# 8_bit_Right_Rev_A.net
KiCad netlist of a schematic drawn in EAGLE
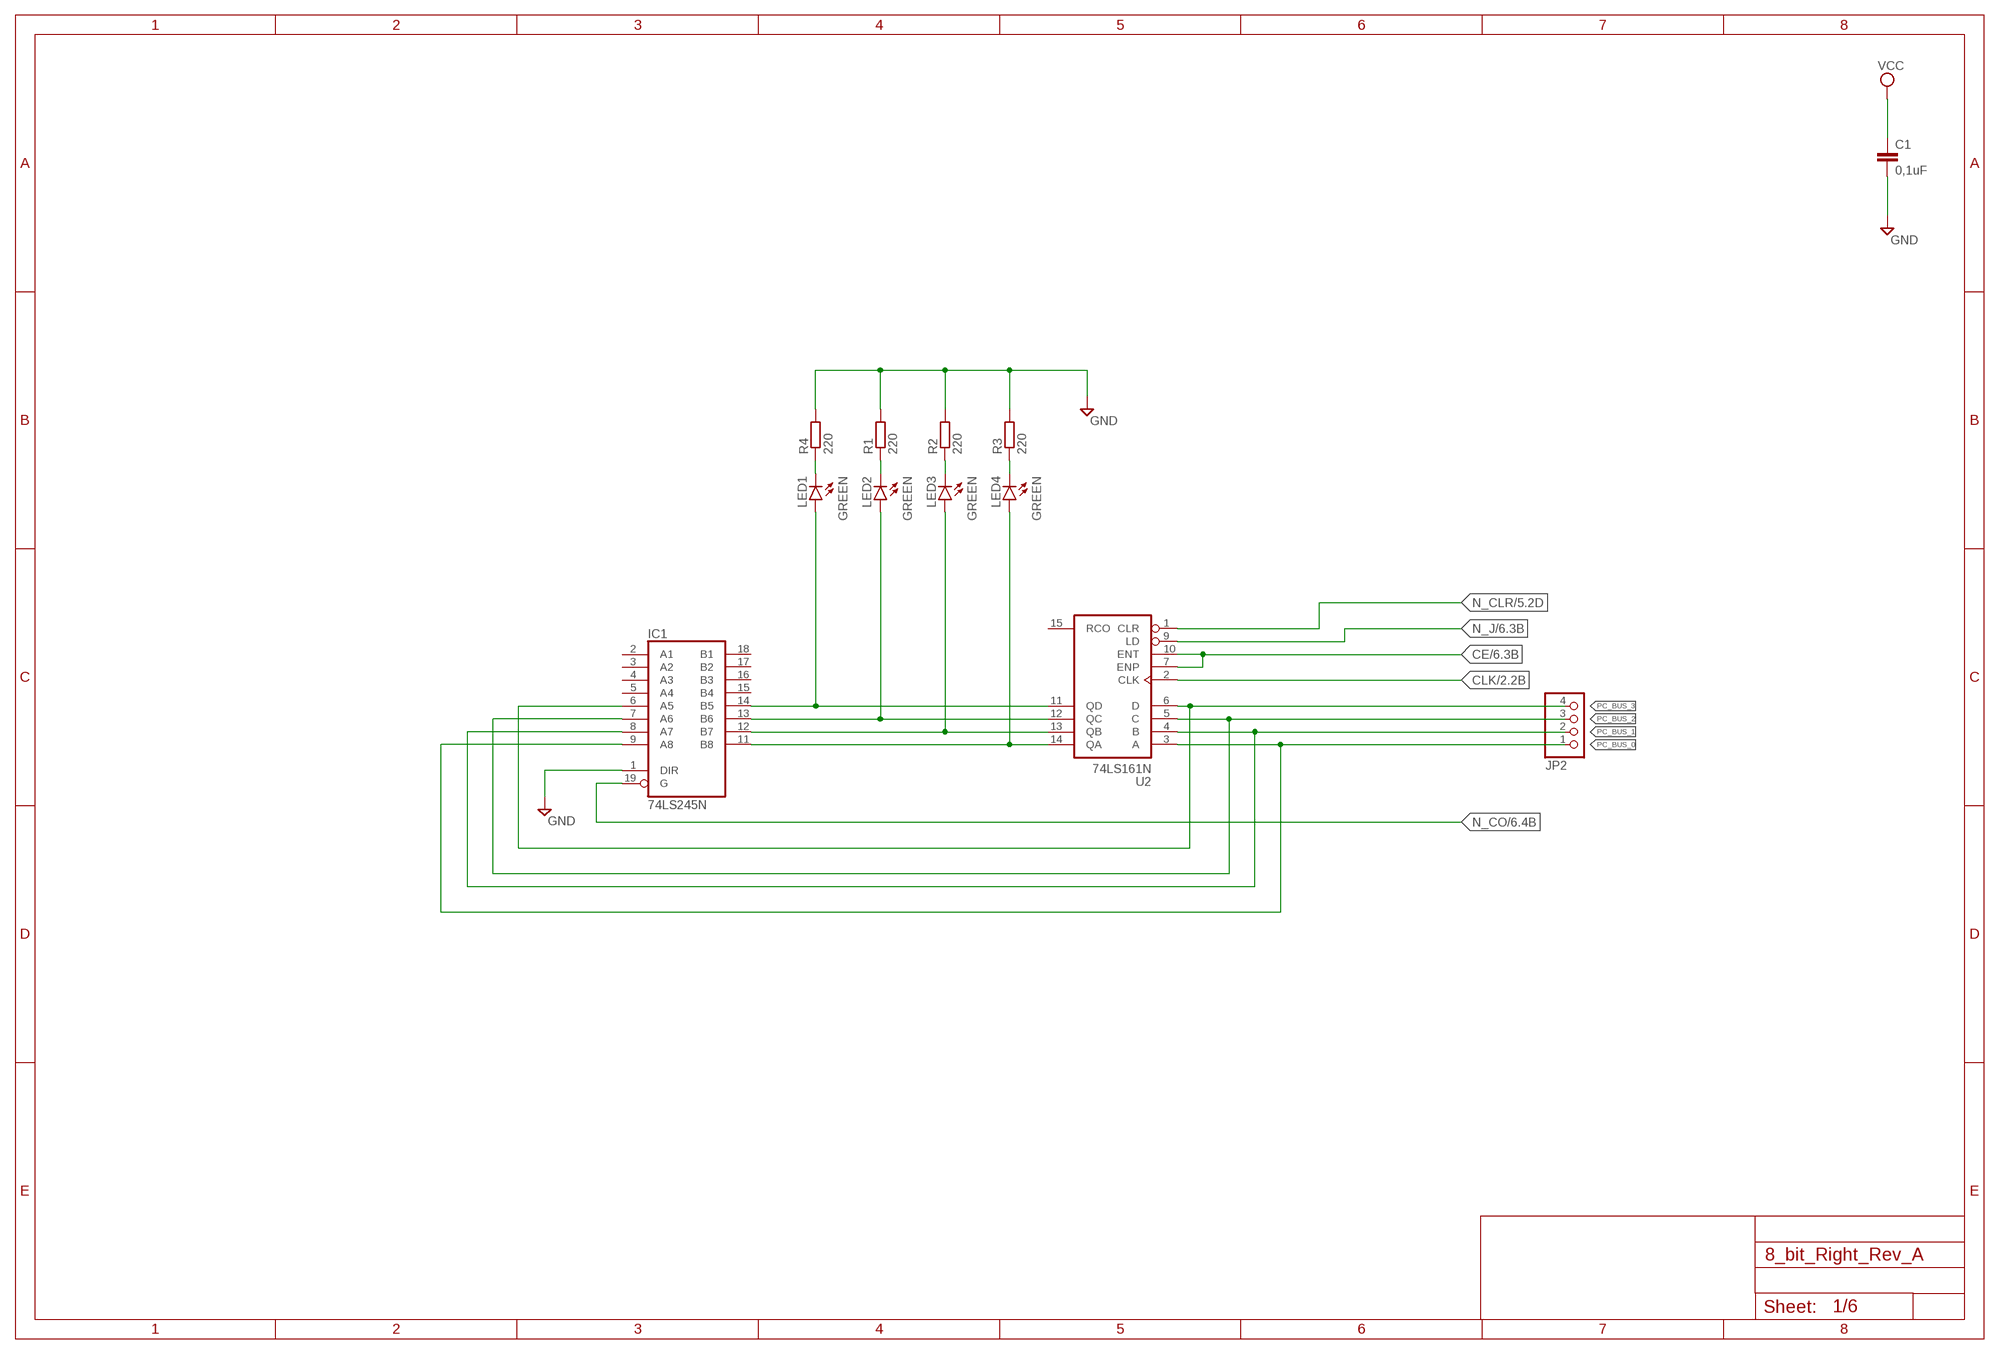
[diagram p0: schematic, sheet 1]
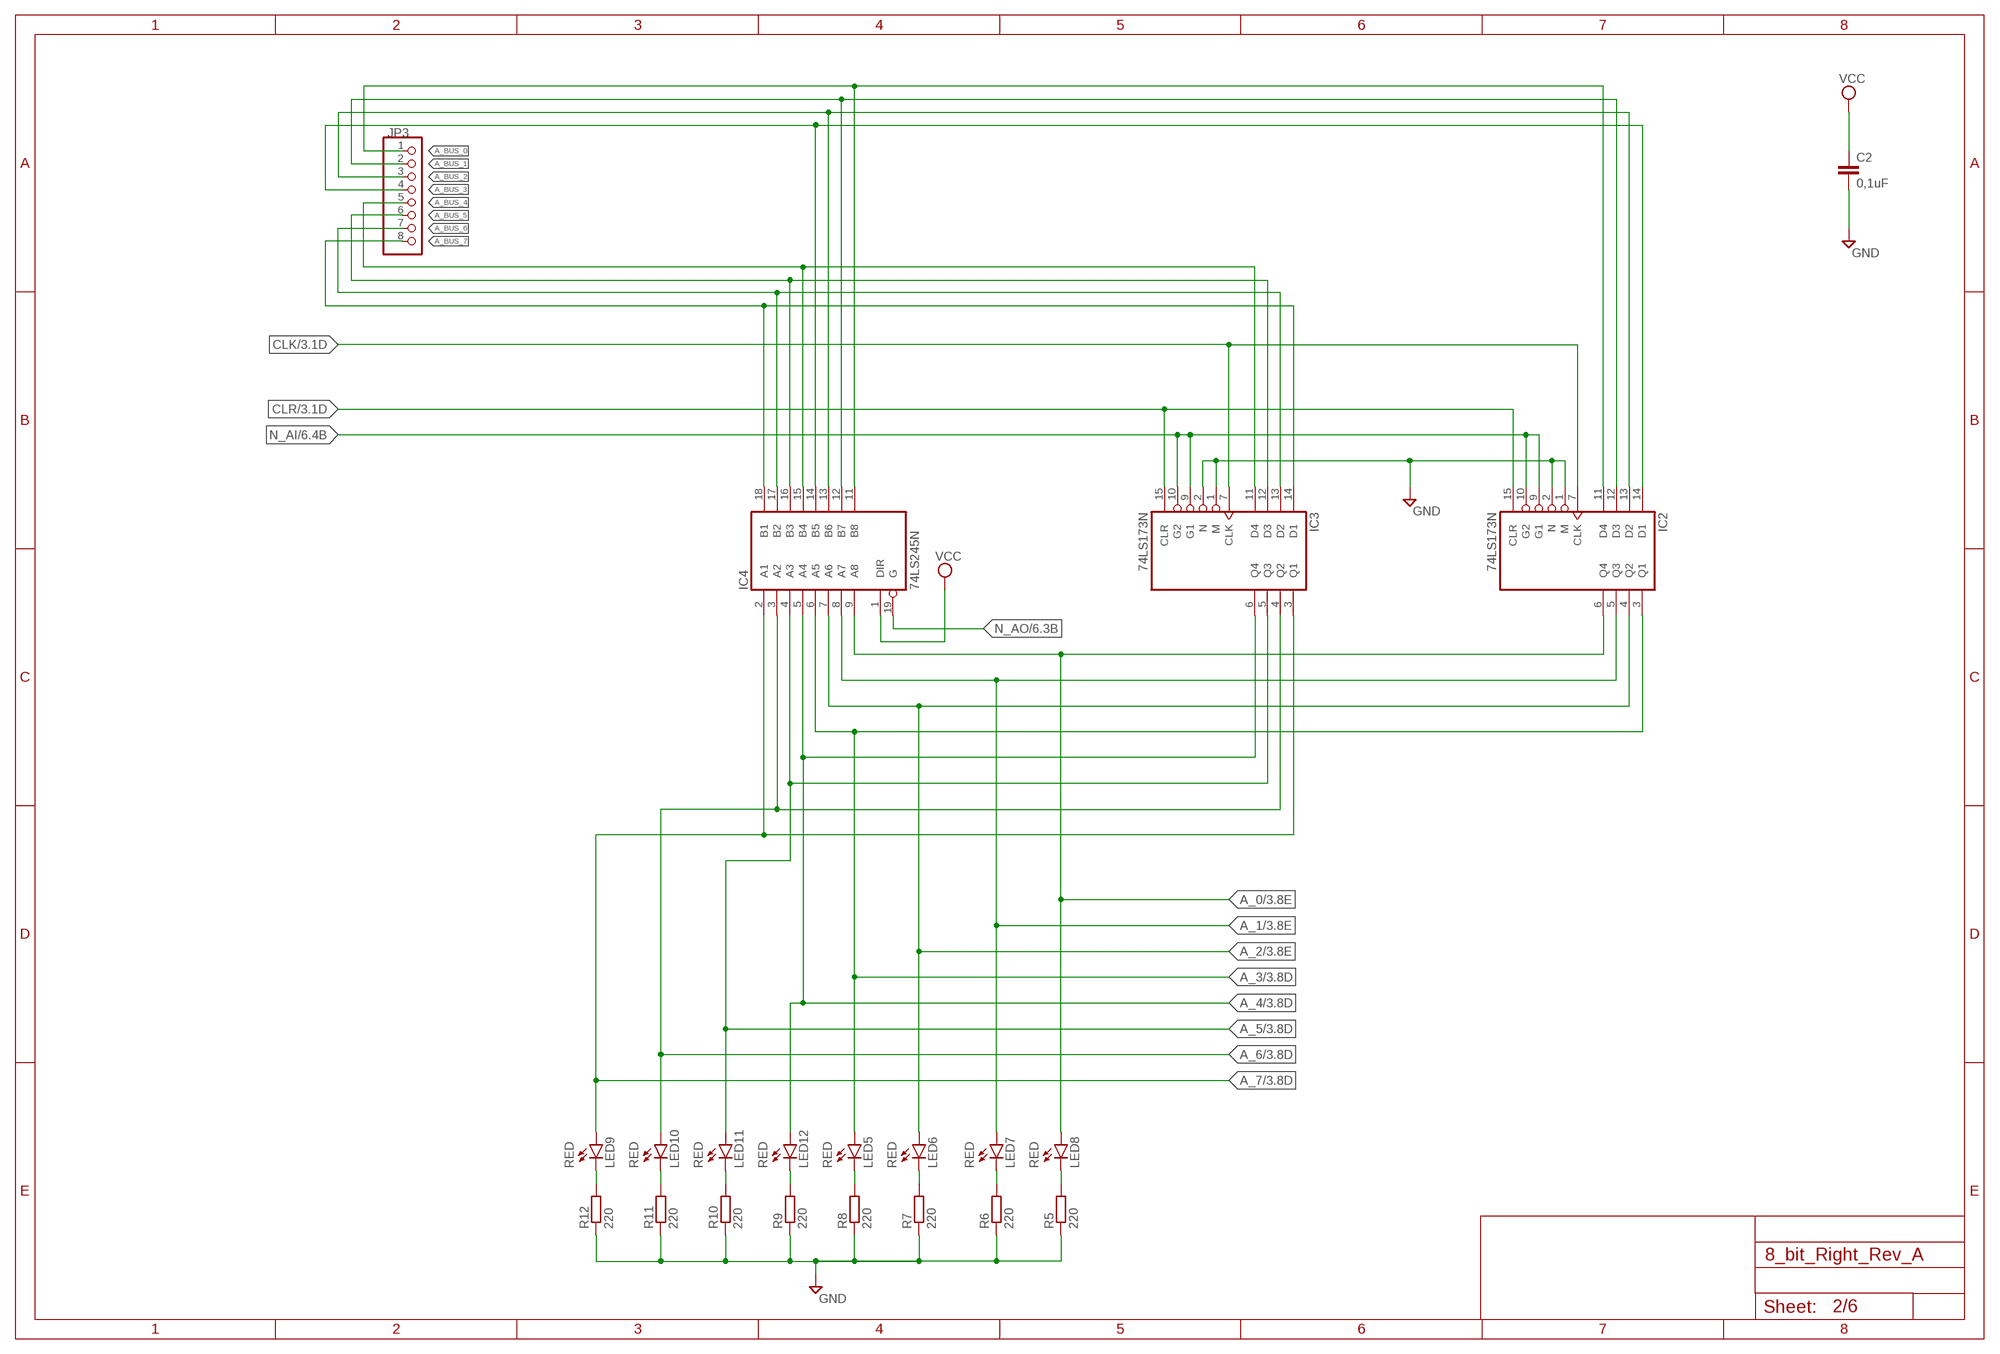
[diagram p1: schematic, sheet 2]
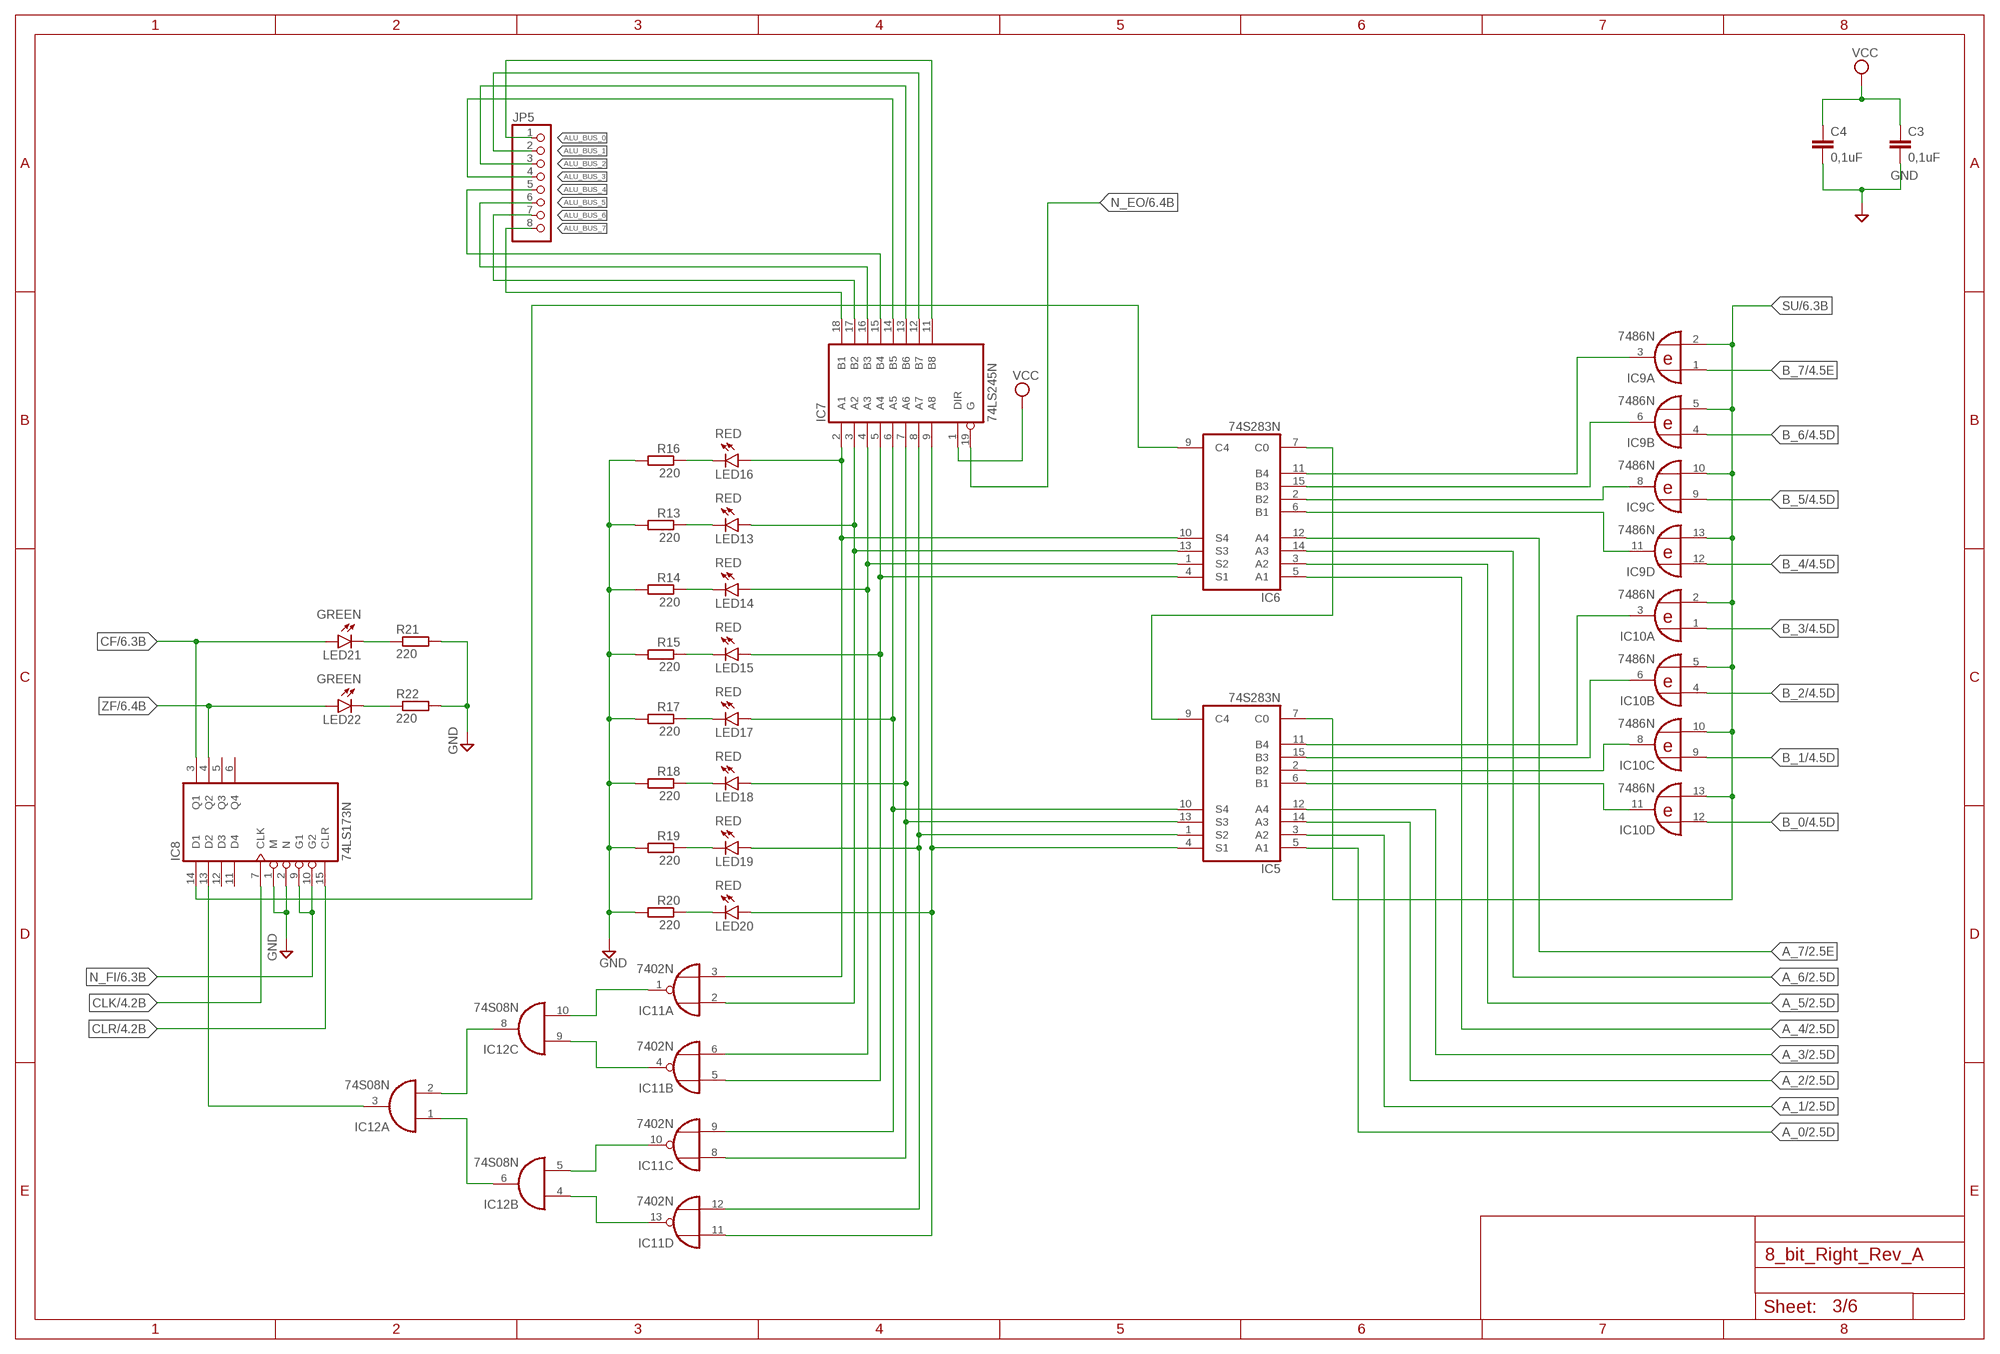
[diagram p2: schematic, sheet 3]
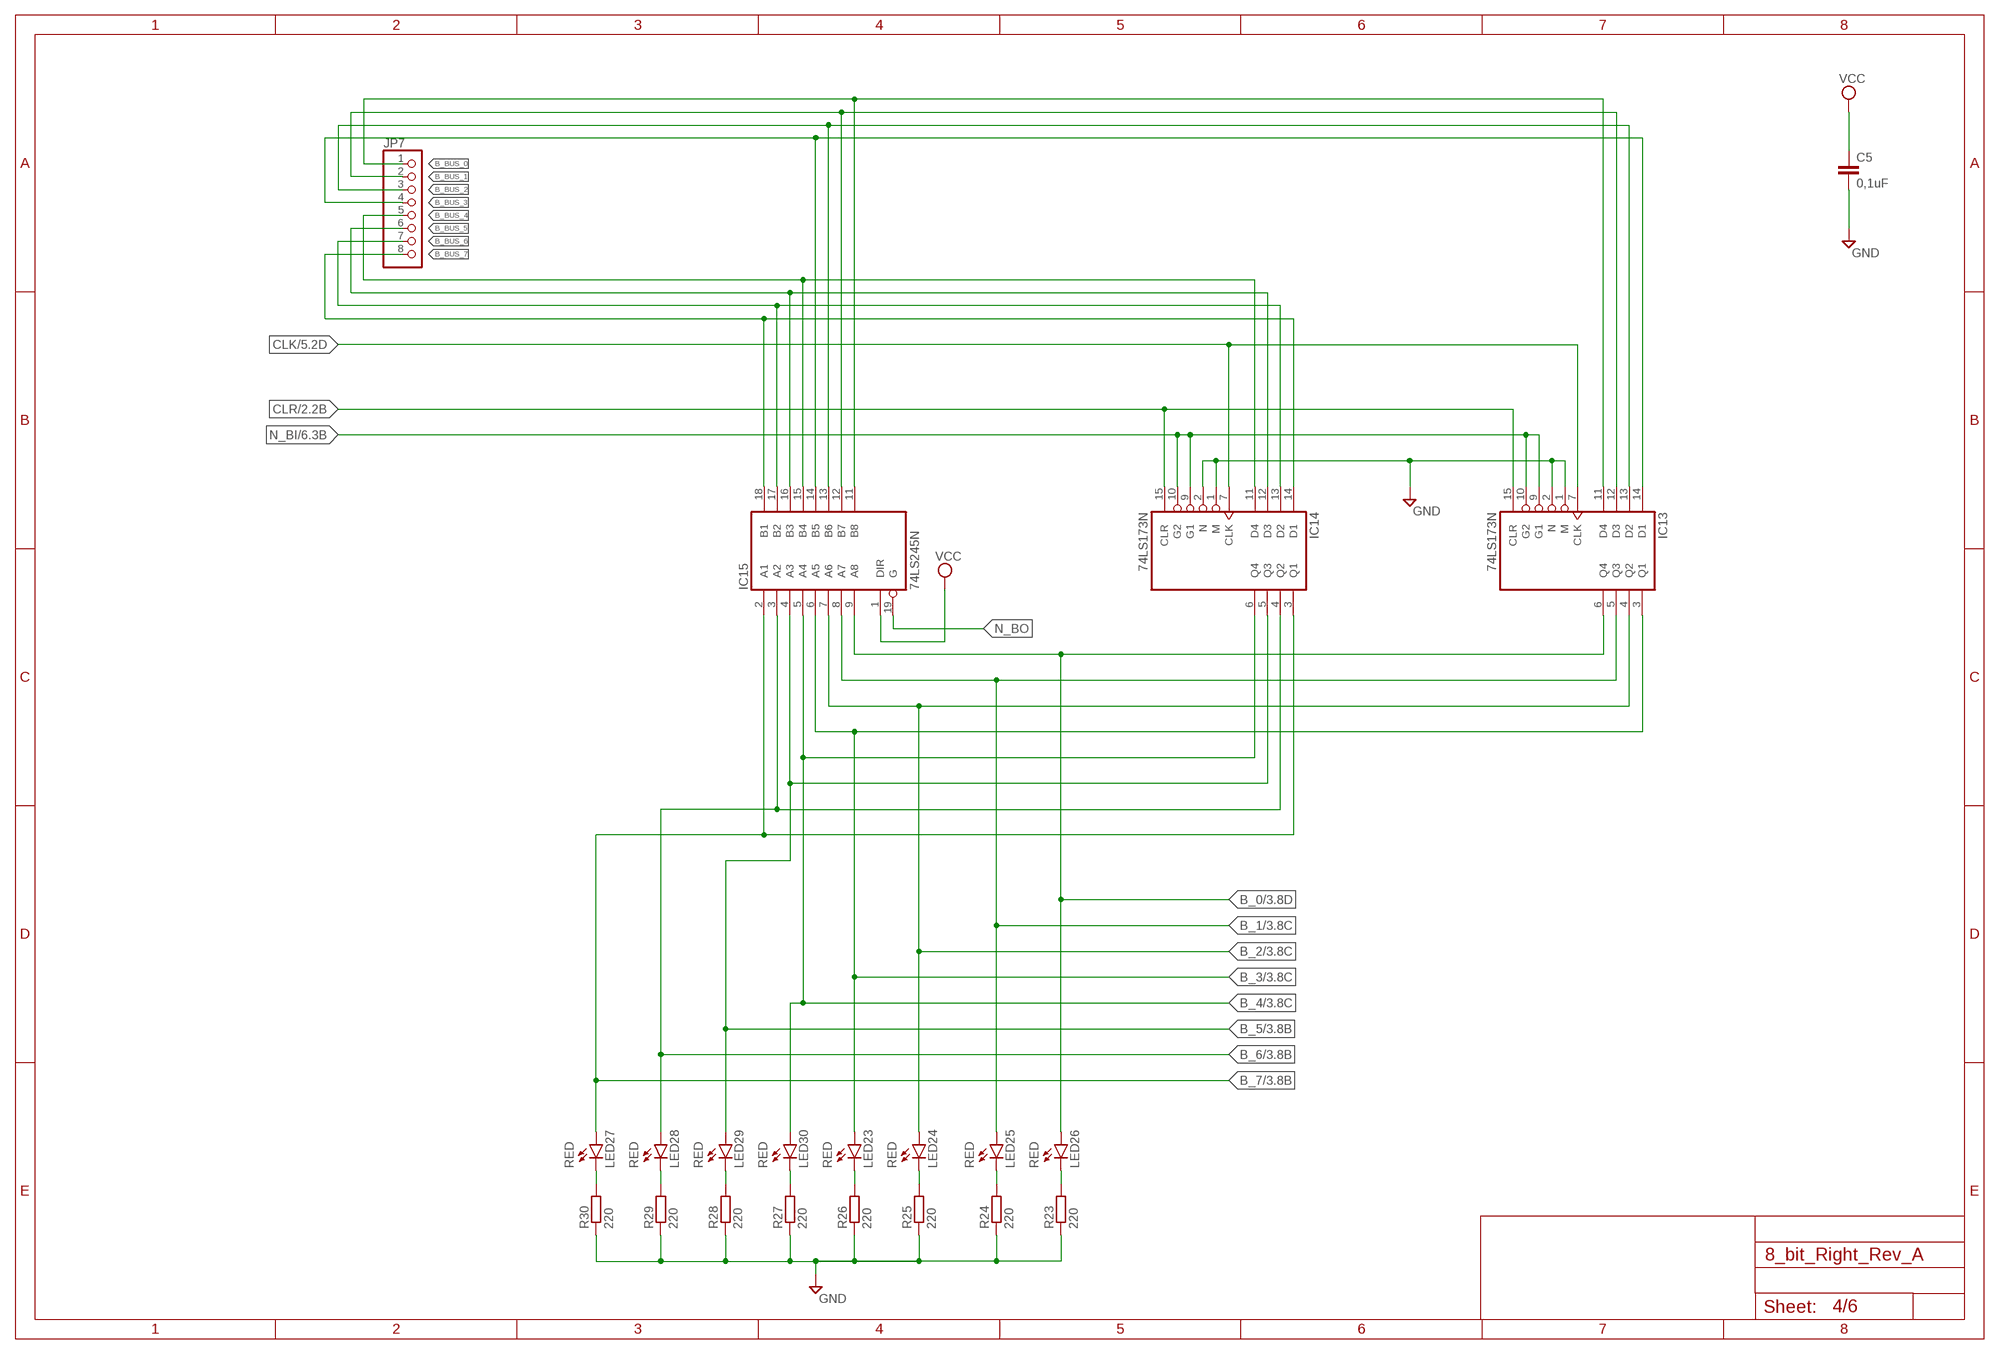
[diagram p3: schematic, sheet 4]
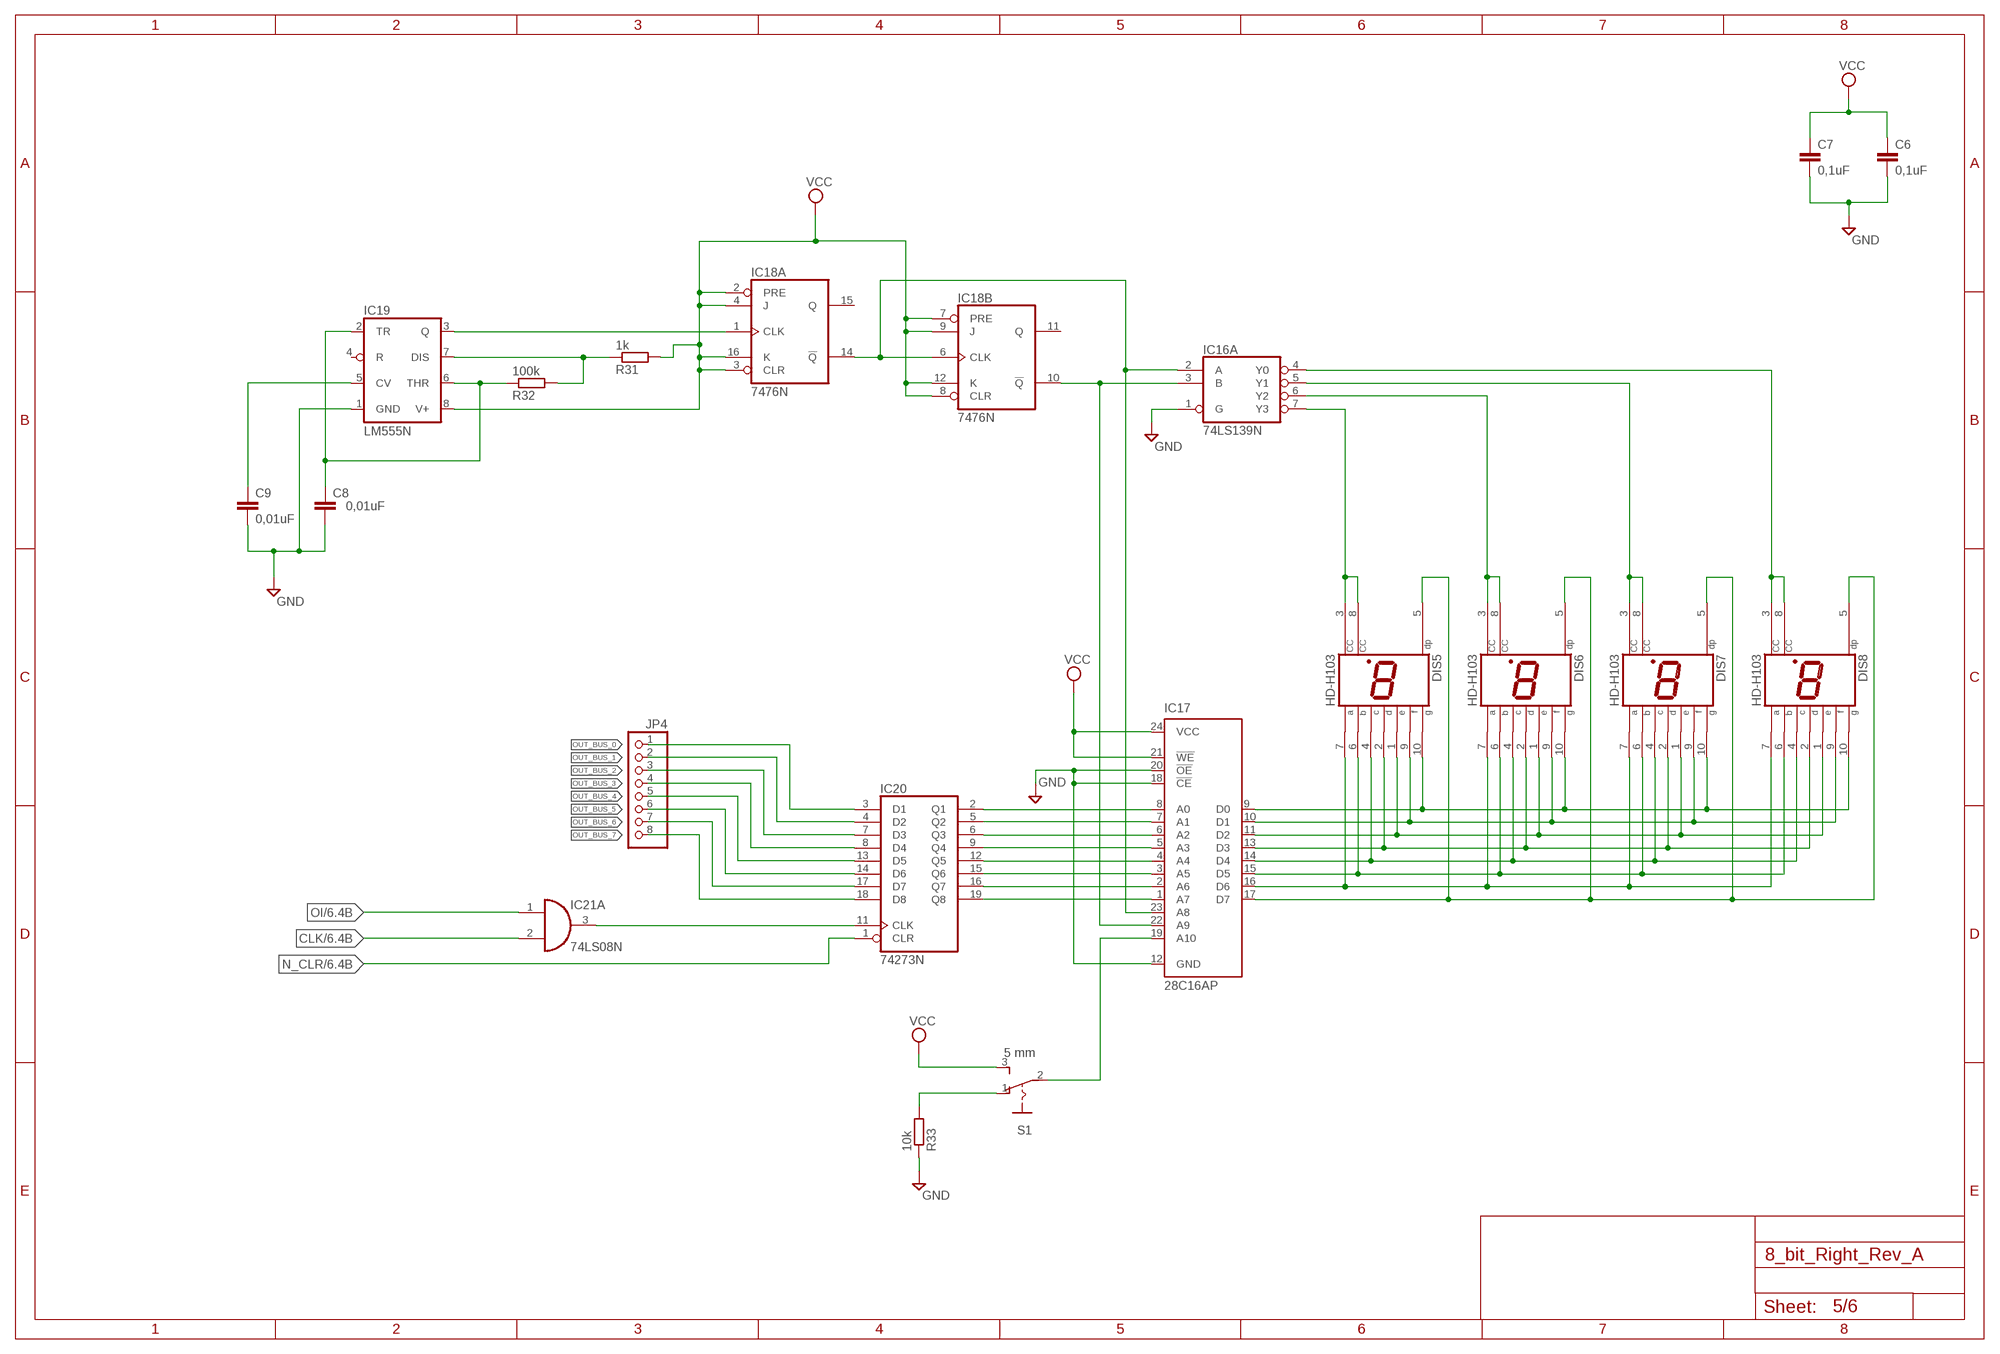
[diagram p4: schematic, sheet 5]
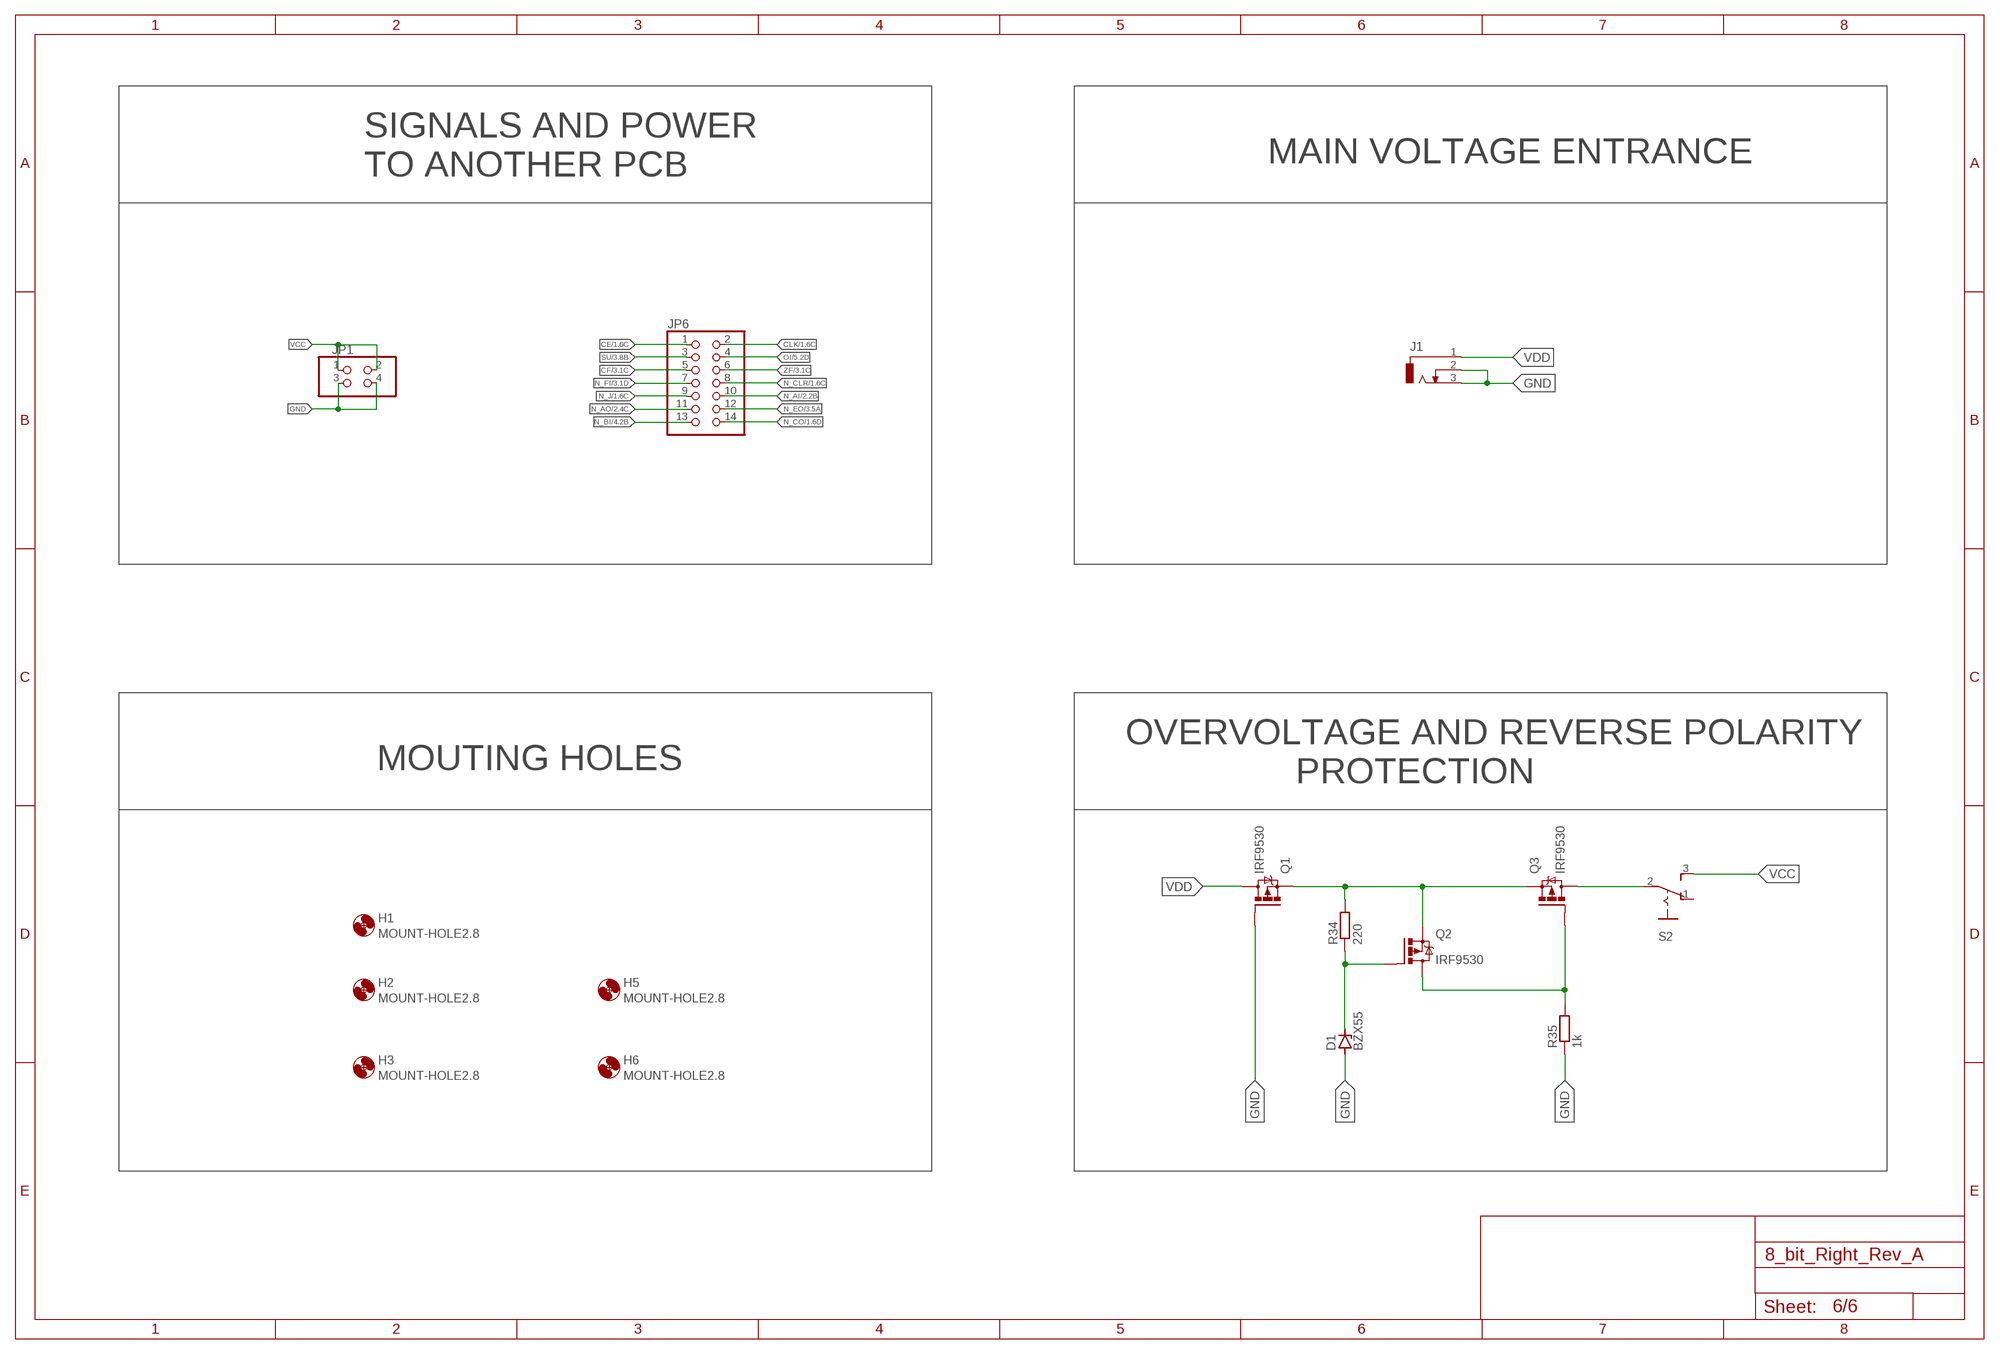
[diagram p5: schematic, sheet 6]

(export (version "E")
  (design (tool "Eeschema 10.0.6"))
  (components
    (comp (ref "D1")
      (value "BZX55")
      (footprint "eagle-import:DO35Z10")
      (libsource (lib "eagle-import") (part "BZX55"))
    )
    (comp (ref "H1")
      (value "MOUNT-HOLE2.8")
      (footprint "eagle-import:2,8")
      (libsource (lib "eagle-import") (part "MOUNT-HOLE2.8"))
    )
    (comp (ref "H2")
      (value "MOUNT-HOLE2.8")
      (footprint "eagle-import:2,8")
      (libsource (lib "eagle-import") (part "MOUNT-HOLE2.8"))
    )
    (comp (ref "H3")
      (value "MOUNT-HOLE2.8")
      (footprint "eagle-import:2,8")
      (libsource (lib "eagle-import") (part "MOUNT-HOLE2.8"))
    )
    (comp (ref "H5")
      (value "MOUNT-HOLE2.8")
      (footprint "eagle-import:2,8")
      (libsource (lib "eagle-import") (part "MOUNT-HOLE2.8"))
    )
    (comp (ref "H6")
      (value "MOUNT-HOLE2.8")
      (footprint "eagle-import:2,8")
      (libsource (lib "eagle-import") (part "MOUNT-HOLE2.8"))
    )
    (comp (ref "J1")
      (value "DCJ0303")
      (footprint "eagle-import:DCJ0303")
      (libsource (lib "eagle-import") (part "DCJ0303"))
    )
    (comp (ref "JP1")
      (value "PINHD-2X2")
      (footprint "eagle-import:2X02")
      (libsource (lib "eagle-import") (part "PINHD-2X2"))
    )
    (comp (ref "JP6")
      (value "PINHD-2X7")
      (footprint "eagle-import:2X07")
      (libsource (lib "eagle-import") (part "PINHD-2X7"))
    )
    (comp (ref "Q1")
      (value "IRF9530")
      (footprint "eagle-import:TO220BV")
      (libsource (lib "eagle-import") (part "IRF9530"))
    )
    (comp (ref "Q2")
      (value "IRF9530")
      (footprint "eagle-import:TO220BV")
      (libsource (lib "eagle-import") (part "IRF9530"))
    )
    (comp (ref "Q3")
      (value "IRF9530")
      (footprint "eagle-import:TO220BV")
      (libsource (lib "eagle-import") (part "IRF9530"))
    )
    (comp (ref "R34")
      (value "220")
      (footprint "eagle-import:0207_10")
      (libsource (lib "eagle-import") (part "R-EU_0207/10"))
    )
    (comp (ref "R35")
      (value "1k")
      (footprint "eagle-import:0207_10")
      (libsource (lib "eagle-import") (part "R-EU_0207/10"))
    )
    (comp (ref "S2")
      (value "255SB")
      (footprint "eagle-import:255SB")
      (libsource (lib "eagle-import") (part "255SB"))
    )
    (comp (ref "C3")
      (value "0,1uF")
      (footprint "eagle-import:C025-030X050")
      (libsource (lib "eagle-import") (part "C-EU025-030X050"))
    )
    (comp (ref "C4")
      (value "0,1uF")
      (footprint "eagle-import:C025-030X050")
      (libsource (lib "eagle-import") (part "C-EU025-030X050"))
    )
    (comp (ref "IC5")
      (value "74S283N")
      (footprint "eagle-import:DIL16")
      (libsource (lib "eagle-import") (part "74283NS"))
    )
    (comp (ref "IC6")
      (value "74S283N")
      (footprint "eagle-import:DIL16")
      (libsource (lib "eagle-import") (part "74283NS"))
    )
    (comp (ref "IC7")
      (value "74LS245N")
      (footprint "eagle-import:DIL20")
      (libsource (lib "eagle-import") (part "74245NLS"))
    )
    (comp (ref "IC8")
      (value "74LS173N")
      (footprint "eagle-import:DIL16")
      (libsource (lib "eagle-import") (part "74173NLS"))
    )
    (comp (ref "IC9")
      (value "7486N")
      (footprint "eagle-import:DIL14")
      (libsource (lib "eagle-import") (part "7486N"))
    )
    (comp (ref "IC10")
      (value "7486N")
      (footprint "eagle-import:DIL14")
      (libsource (lib "eagle-import") (part "7486N"))
    )
    (comp (ref "IC11")
      (value "7402N")
      (footprint "eagle-import:DIL14")
      (libsource (lib "eagle-import") (part "7402N"))
    )
    (comp (ref "IC12")
      (value "74S08N")
      (footprint "eagle-import:DIL14")
      (libsource (lib "eagle-import") (part "74xx-eu_85_7408NS"))
    )
    (comp (ref "JP5")
      (value "PINHD-1X8")
      (footprint "eagle-import:1X08")
      (libsource (lib "eagle-import") (part "PINHD-1X8"))
    )
    (comp (ref "LED13")
      (value "RED")
      (footprint "eagle-import:LED5MM")
      (libsource (lib "eagle-import") (part "LED5MM"))
    )
    (comp (ref "LED14")
      (value "RED")
      (footprint "eagle-import:LED5MM")
      (libsource (lib "eagle-import") (part "LED5MM"))
    )
    (comp (ref "LED15")
      (value "RED")
      (footprint "eagle-import:LED5MM")
      (libsource (lib "eagle-import") (part "LED5MM"))
    )
    (comp (ref "LED16")
      (value "RED")
      (footprint "eagle-import:LED5MM")
      (libsource (lib "eagle-import") (part "LED5MM"))
    )
    (comp (ref "LED17")
      (value "RED")
      (footprint "eagle-import:LED5MM")
      (libsource (lib "eagle-import") (part "LED5MM"))
    )
    (comp (ref "LED18")
      (value "RED")
      (footprint "eagle-import:LED5MM")
      (libsource (lib "eagle-import") (part "LED5MM"))
    )
    (comp (ref "LED19")
      (value "RED")
      (footprint "eagle-import:LED5MM")
      (libsource (lib "eagle-import") (part "LED5MM"))
    )
    (comp (ref "LED20")
      (value "RED")
      (footprint "eagle-import:LED5MM")
      (libsource (lib "eagle-import") (part "LED5MM"))
    )
    (comp (ref "LED21")
      (value "GREEN")
      (footprint "eagle-import:LED5MM")
      (libsource (lib "eagle-import") (part "LED5MM"))
    )
    (comp (ref "LED22")
      (value "GREEN")
      (footprint "eagle-import:LED5MM")
      (libsource (lib "eagle-import") (part "LED5MM"))
    )
    (comp (ref "R13")
      (value "220")
      (footprint "eagle-import:0207_10")
      (libsource (lib "eagle-import") (part "R-EU_0207/10"))
    )
    (comp (ref "R14")
      (value "220")
      (footprint "eagle-import:0207_10")
      (libsource (lib "eagle-import") (part "R-EU_0207/10"))
    )
    (comp (ref "R15")
      (value "220")
      (footprint "eagle-import:0207_10")
      (libsource (lib "eagle-import") (part "R-EU_0207/10"))
    )
    (comp (ref "R16")
      (value "220")
      (footprint "eagle-import:0207_10")
      (libsource (lib "eagle-import") (part "R-EU_0207/10"))
    )
    (comp (ref "R17")
      (value "220")
      (footprint "eagle-import:0207_10")
      (libsource (lib "eagle-import") (part "R-EU_0207/10"))
    )
    (comp (ref "R18")
      (value "220")
      (footprint "eagle-import:0207_10")
      (libsource (lib "eagle-import") (part "R-EU_0207/10"))
    )
    (comp (ref "R19")
      (value "220")
      (footprint "eagle-import:0207_10")
      (libsource (lib "eagle-import") (part "R-EU_0207/10"))
    )
    (comp (ref "R20")
      (value "220")
      (footprint "eagle-import:0207_10")
      (libsource (lib "eagle-import") (part "R-EU_0207/10"))
    )
    (comp (ref "R21")
      (value "220")
      (footprint "eagle-import:0207_10")
      (libsource (lib "eagle-import") (part "R-EU_0207/10"))
    )
    (comp (ref "R22")
      (value "220")
      (footprint "eagle-import:0207_10")
      (libsource (lib "eagle-import") (part "R-EU_0207/10"))
    )
    (comp (ref "C6")
      (value "0,1uF")
      (footprint "eagle-import:C025-030X050")
      (libsource (lib "eagle-import") (part "C-EU025-030X050"))
    )
    (comp (ref "C7")
      (value "0,1uF")
      (footprint "eagle-import:C025-030X050")
      (libsource (lib "eagle-import") (part "C-EU025-030X050"))
    )
    (comp (ref "C8")
      (value "0,01uF")
      (footprint "eagle-import:C025-030X050")
      (libsource (lib "eagle-import") (part "C-EU025-030X050"))
    )
    (comp (ref "C9")
      (value "0,01uF")
      (footprint "eagle-import:C025-030X050")
      (libsource (lib "eagle-import") (part "C-EU025-030X050"))
    )
    (comp (ref "DIS5")
      (value "HD-H103")
      (footprint "eagle-import:HDSP-M")
      (libsource (lib "eagle-import") (part "HD-H103"))
    )
    (comp (ref "DIS6")
      (value "HD-H103")
      (footprint "eagle-import:HDSP-M")
      (libsource (lib "eagle-import") (part "HD-H103"))
    )
    (comp (ref "DIS7")
      (value "HD-H103")
      (footprint "eagle-import:HDSP-M")
      (libsource (lib "eagle-import") (part "HD-H103"))
    )
    (comp (ref "DIS8")
      (value "HD-H103")
      (footprint "eagle-import:HDSP-M")
      (libsource (lib "eagle-import") (part "HD-H103"))
    )
    (comp (ref "IC16")
      (value "74LS139N")
      (footprint "eagle-import:DIL16")
      (libsource (lib "eagle-import") (part "74139NLS"))
    )
    (comp (ref "IC17")
      (value "28C16AP")
      (footprint "eagle-import:DIL24-6")
      (fields (field (name "MPN") "CAT28C16ALI-12"))
      (libsource (lib "eagle-import") (part "2816APC"))
    )
    (comp (ref "IC18")
      (value "7476N")
      (footprint "eagle-import:DIL16")
      (libsource (lib "eagle-import") (part "7476N"))
    )
    (comp (ref "IC19")
      (value "LM555N")
      (footprint "eagle-import:DIL08")
      (libsource (lib "eagle-import") (part "555NLM"))
    )
    (comp (ref "IC20")
      (value "74273N")
      (footprint "eagle-import:DIL20")
      (libsource (lib "eagle-import") (part "74273N"))
    )
    (comp (ref "IC21")
      (value "74LS08N")
      (footprint "eagle-import:DIL14")
      (libsource (lib "eagle-import") (part "7408NLS"))
    )
    (comp (ref "JP4")
      (value "PINHD-1X8")
      (footprint "eagle-import:1X08")
      (libsource (lib "eagle-import") (part "PINHD-1X8"))
    )
    (comp (ref "R31")
      (value "1k")
      (footprint "eagle-import:0207_10")
      (libsource (lib "eagle-import") (part "R-EU_0207/10"))
    )
    (comp (ref "R32")
      (value "100k")
      (footprint "eagle-import:0207_10")
      (libsource (lib "eagle-import") (part "R-EU_0207/10"))
    )
    (comp (ref "R33")
      (value "10k")
      (footprint "eagle-import:0207_10")
      (libsource (lib "eagle-import") (part "R-EU_0207/10"))
    )
    (comp (ref "S1")
      (value "5 mm")
      (footprint "eagle-import:255SB")
      (libsource (lib "eagle-import") (part "255SB"))
    )
    (comp (ref "C5")
      (value "0,1uF")
      (footprint "eagle-import:C025-030X050")
      (libsource (lib "eagle-import") (part "C-EU025-030X050"))
    )
    (comp (ref "IC13")
      (value "74LS173N")
      (footprint "eagle-import:DIL16")
      (libsource (lib "eagle-import") (part "74173NLS"))
    )
    (comp (ref "IC14")
      (value "74LS173N")
      (footprint "eagle-import:DIL16")
      (libsource (lib "eagle-import") (part "74173NLS"))
    )
    (comp (ref "IC15")
      (value "74LS245N")
      (footprint "eagle-import:DIL20")
      (libsource (lib "eagle-import") (part "74245NLS"))
    )
    (comp (ref "JP7")
      (value "PINHD-1X8")
      (footprint "eagle-import:1X08")
      (libsource (lib "eagle-import") (part "PINHD-1X8"))
    )
    (comp (ref "LED23")
      (value "RED")
      (footprint "eagle-import:LED5MM")
      (libsource (lib "eagle-import") (part "LED5MM"))
    )
    (comp (ref "LED24")
      (value "RED")
      (footprint "eagle-import:LED5MM")
      (libsource (lib "eagle-import") (part "LED5MM"))
    )
    (comp (ref "LED25")
      (value "RED")
      (footprint "eagle-import:LED5MM")
      (libsource (lib "eagle-import") (part "LED5MM"))
    )
    (comp (ref "LED26")
      (value "RED")
      (footprint "eagle-import:LED5MM")
      (libsource (lib "eagle-import") (part "LED5MM"))
    )
    (comp (ref "LED27")
      (value "RED")
      (footprint "eagle-import:LED5MM")
      (libsource (lib "eagle-import") (part "LED5MM"))
    )
    (comp (ref "LED28")
      (value "RED")
      (footprint "eagle-import:LED5MM")
      (libsource (lib "eagle-import") (part "LED5MM"))
    )
    (comp (ref "LED29")
      (value "RED")
      (footprint "eagle-import:LED5MM")
      (libsource (lib "eagle-import") (part "LED5MM"))
    )
    (comp (ref "LED30")
      (value "RED")
      (footprint "eagle-import:LED5MM")
      (libsource (lib "eagle-import") (part "LED5MM"))
    )
    (comp (ref "R23")
      (value "220")
      (footprint "eagle-import:0207_10")
      (libsource (lib "eagle-import") (part "R-EU_0207/10"))
    )
    (comp (ref "R24")
      (value "220")
      (footprint "eagle-import:0207_10")
      (libsource (lib "eagle-import") (part "R-EU_0207/10"))
    )
    (comp (ref "R25")
      (value "220")
      (footprint "eagle-import:0207_10")
      (libsource (lib "eagle-import") (part "R-EU_0207/10"))
    )
    (comp (ref "R26")
      (value "220")
      (footprint "eagle-import:0207_10")
      (libsource (lib "eagle-import") (part "R-EU_0207/10"))
    )
    (comp (ref "R27")
      (value "220")
      (footprint "eagle-import:0207_10")
      (libsource (lib "eagle-import") (part "R-EU_0207/10"))
    )
    (comp (ref "R28")
      (value "220")
      (footprint "eagle-import:0207_10")
      (libsource (lib "eagle-import") (part "R-EU_0207/10"))
    )
    (comp (ref "R29")
      (value "220")
      (footprint "eagle-import:0207_10")
      (libsource (lib "eagle-import") (part "R-EU_0207/10"))
    )
    (comp (ref "R30")
      (value "220")
      (footprint "eagle-import:0207_10")
      (libsource (lib "eagle-import") (part "R-EU_0207/10"))
    )
    (comp (ref "C1")
      (value "0,1uF")
      (footprint "eagle-import:C025-030X050")
      (libsource (lib "eagle-import") (part "C-EU025-030X050"))
    )
    (comp (ref "IC1")
      (value "74LS245N")
      (footprint "eagle-import:DIL20")
      (libsource (lib "eagle-import") (part "74245NLS"))
    )
    (comp (ref "JP2")
      (value "PINHD-1X4")
      (footprint "eagle-import:1X04")
      (libsource (lib "eagle-import") (part "PINHD-1X4"))
    )
    (comp (ref "LED1")
      (value "GREEN")
      (footprint "eagle-import:LED5MM")
      (libsource (lib "eagle-import") (part "LED5MM"))
    )
    (comp (ref "LED2")
      (value "GREEN")
      (footprint "eagle-import:LED5MM")
      (libsource (lib "eagle-import") (part "LED5MM"))
    )
    (comp (ref "LED3")
      (value "GREEN")
      (footprint "eagle-import:LED5MM")
      (libsource (lib "eagle-import") (part "LED5MM"))
    )
    (comp (ref "LED4")
      (value "GREEN")
      (footprint "eagle-import:LED5MM")
      (libsource (lib "eagle-import") (part "LED5MM"))
    )
    (comp (ref "R1")
      (value "220")
      (footprint "eagle-import:0207_10")
      (libsource (lib "eagle-import") (part "R-EU_0207/10"))
    )
    (comp (ref "R2")
      (value "220")
      (footprint "eagle-import:0207_10")
      (libsource (lib "eagle-import") (part "R-EU_0207/10"))
    )
    (comp (ref "R3")
      (value "220")
      (footprint "eagle-import:0207_10")
      (libsource (lib "eagle-import") (part "R-EU_0207/10"))
    )
    (comp (ref "R4")
      (value "220")
      (footprint "eagle-import:0207_10")
      (libsource (lib "eagle-import") (part "R-EU_0207/10"))
    )
    (comp (ref "U2")
      (value "74LS161N")
      (footprint "eagle-import:DIL16")
      (libsource (lib "eagle-import") (part "74161NLS"))
    )
    (comp (ref "C2")
      (value "0,1uF")
      (footprint "eagle-import:C025-030X050")
      (libsource (lib "eagle-import") (part "C-EU025-030X050"))
    )
    (comp (ref "IC2")
      (value "74LS173N")
      (footprint "eagle-import:DIL16")
      (libsource (lib "eagle-import") (part "74173NLS"))
    )
    (comp (ref "IC3")
      (value "74LS173N")
      (footprint "eagle-import:DIL16")
      (libsource (lib "eagle-import") (part "74173NLS"))
    )
    (comp (ref "IC4")
      (value "74LS245N")
      (footprint "eagle-import:DIL20")
      (libsource (lib "eagle-import") (part "74245NLS"))
    )
    (comp (ref "JP3")
      (value "PINHD-1X8")
      (footprint "eagle-import:1X08")
      (libsource (lib "eagle-import") (part "PINHD-1X8"))
    )
    (comp (ref "LED5")
      (value "RED")
      (footprint "eagle-import:LED5MM")
      (libsource (lib "eagle-import") (part "LED5MM"))
    )
    (comp (ref "LED6")
      (value "RED")
      (footprint "eagle-import:LED5MM")
      (libsource (lib "eagle-import") (part "LED5MM"))
    )
    (comp (ref "LED7")
      (value "RED")
      (footprint "eagle-import:LED5MM")
      (libsource (lib "eagle-import") (part "LED5MM"))
    )
    (comp (ref "LED8")
      (value "RED")
      (footprint "eagle-import:LED5MM")
      (libsource (lib "eagle-import") (part "LED5MM"))
    )
    (comp (ref "LED9")
      (value "RED")
      (footprint "eagle-import:LED5MM")
      (libsource (lib "eagle-import") (part "LED5MM"))
    )
    (comp (ref "LED10")
      (value "RED")
      (footprint "eagle-import:LED5MM")
      (libsource (lib "eagle-import") (part "LED5MM"))
    )
    (comp (ref "LED11")
      (value "RED")
      (footprint "eagle-import:LED5MM")
      (libsource (lib "eagle-import") (part "LED5MM"))
    )
    (comp (ref "LED12")
      (value "RED")
      (footprint "eagle-import:LED5MM")
      (libsource (lib "eagle-import") (part "LED5MM"))
    )
    (comp (ref "R5")
      (value "220")
      (footprint "eagle-import:0207_10")
      (libsource (lib "eagle-import") (part "R-EU_0207/10"))
    )
    (comp (ref "R6")
      (value "220")
      (footprint "eagle-import:0207_10")
      (libsource (lib "eagle-import") (part "R-EU_0207/10"))
    )
    (comp (ref "R7")
      (value "220")
      (footprint "eagle-import:0207_10")
      (libsource (lib "eagle-import") (part "R-EU_0207/10"))
    )
    (comp (ref "R8")
      (value "220")
      (footprint "eagle-import:0207_10")
      (libsource (lib "eagle-import") (part "R-EU_0207/10"))
    )
    (comp (ref "R9")
      (value "220")
      (footprint "eagle-import:0207_10")
      (libsource (lib "eagle-import") (part "R-EU_0207/10"))
    )
    (comp (ref "R10")
      (value "220")
      (footprint "eagle-import:0207_10")
      (libsource (lib "eagle-import") (part "R-EU_0207/10"))
    )
    (comp (ref "R11")
      (value "220")
      (footprint "eagle-import:0207_10")
      (libsource (lib "eagle-import") (part "R-EU_0207/10"))
    )
    (comp (ref "R12")
      (value "220")
      (footprint "eagle-import:0207_10")
      (libsource (lib "eagle-import") (part "R-EU_0207/10"))
    )
  )
  (nets
    (net (code "1") (name "ALU_BUS_0") (class "Default")
      (node (ref "IC7") (pin "11") (pinfunction "B8_11") (pintype "bidirectional"))
      (node (ref "JP5") (pin "1") (pinfunction "1_1") (pintype "passive"))
    )
    (net (code "2") (name "ALU_BUS_1") (class "Default")
      (node (ref "IC7") (pin "12") (pinfunction "B7_12") (pintype "bidirectional"))
      (node (ref "JP5") (pin "2") (pinfunction "2_2") (pintype "passive"))
    )
    (net (code "3") (name "ALU_BUS_2") (class "Default")
      (node (ref "IC7") (pin "13") (pinfunction "B6_13") (pintype "bidirectional"))
      (node (ref "JP5") (pin "3") (pinfunction "3_3") (pintype "passive"))
    )
    (net (code "4") (name "ALU_BUS_3") (class "Default")
      (node (ref "IC7") (pin "14") (pinfunction "B5_14") (pintype "bidirectional"))
      (node (ref "JP5") (pin "4") (pinfunction "4_4") (pintype "passive"))
    )
    (net (code "5") (name "ALU_BUS_4") (class "Default")
      (node (ref "IC7") (pin "15") (pinfunction "B4_15") (pintype "bidirectional"))
      (node (ref "JP5") (pin "5") (pinfunction "5_5") (pintype "passive"))
    )
    (net (code "6") (name "ALU_BUS_5") (class "Default")
      (node (ref "IC7") (pin "16") (pinfunction "B3_16") (pintype "bidirectional"))
      (node (ref "JP5") (pin "6") (pinfunction "6_6") (pintype "passive"))
    )
    (net (code "7") (name "ALU_BUS_6") (class "Default")
      (node (ref "IC7") (pin "17") (pinfunction "B2_17") (pintype "bidirectional"))
      (node (ref "JP5") (pin "7") (pinfunction "7_7") (pintype "passive"))
    )
    (net (code "8") (name "ALU_BUS_7") (class "Default")
      (node (ref "IC7") (pin "18") (pinfunction "B1_18") (pintype "bidirectional"))
      (node (ref "JP5") (pin "8") (pinfunction "8_8") (pintype "passive"))
    )
    (net (code "9") (name "A_0") (class "Default")
      (node (ref "IC2") (pin "6") (pinfunction "Q4_6") (pintype "tri_state"))
      (node (ref "IC4") (pin "9") (pinfunction "A8_9") (pintype "bidirectional"))
      (node (ref "IC5") (pin "5") (pinfunction "A1_5") (pintype "input"))
      (node (ref "LED8") (pin "A") (pinfunction "A_A") (pintype "passive"))
    )
    (net (code "10") (name "A_1") (class "Default")
      (node (ref "IC2") (pin "5") (pinfunction "Q3_5") (pintype "tri_state"))
      (node (ref "IC4") (pin "8") (pinfunction "A7_8") (pintype "bidirectional"))
      (node (ref "IC5") (pin "3") (pinfunction "A2_3") (pintype "input"))
      (node (ref "LED7") (pin "A") (pinfunction "A_A") (pintype "passive"))
    )
    (net (code "11") (name "A_2") (class "Default")
      (node (ref "IC2") (pin "4") (pinfunction "Q2_4") (pintype "tri_state"))
      (node (ref "IC4") (pin "7") (pinfunction "A6_7") (pintype "bidirectional"))
      (node (ref "IC5") (pin "14") (pinfunction "A3_14") (pintype "input"))
      (node (ref "LED6") (pin "A") (pinfunction "A_A") (pintype "passive"))
    )
    (net (code "12") (name "A_3") (class "Default")
      (node (ref "IC2") (pin "3") (pinfunction "Q1_3") (pintype "tri_state"))
      (node (ref "IC4") (pin "6") (pinfunction "A5_6") (pintype "bidirectional"))
      (node (ref "IC5") (pin "12") (pinfunction "A4_12") (pintype "input"))
      (node (ref "LED5") (pin "A") (pinfunction "A_A") (pintype "passive"))
    )
    (net (code "13") (name "A_4") (class "Default")
      (node (ref "IC3") (pin "6") (pinfunction "Q4_6") (pintype "tri_state"))
      (node (ref "IC4") (pin "5") (pinfunction "A4_5") (pintype "bidirectional"))
      (node (ref "IC6") (pin "5") (pinfunction "A1_5") (pintype "input"))
      (node (ref "LED12") (pin "A") (pinfunction "A_A") (pintype "passive"))
    )
    (net (code "14") (name "A_5") (class "Default")
      (node (ref "IC3") (pin "5") (pinfunction "Q3_5") (pintype "tri_state"))
      (node (ref "IC4") (pin "4") (pinfunction "A3_4") (pintype "bidirectional"))
      (node (ref "IC6") (pin "3") (pinfunction "A2_3") (pintype "input"))
      (node (ref "LED11") (pin "A") (pinfunction "A_A") (pintype "passive"))
    )
    (net (code "15") (name "A_6") (class "Default")
      (node (ref "IC3") (pin "4") (pinfunction "Q2_4") (pintype "tri_state"))
      (node (ref "IC4") (pin "3") (pinfunction "A2_3") (pintype "bidirectional"))
      (node (ref "IC6") (pin "14") (pinfunction "A3_14") (pintype "input"))
      (node (ref "LED10") (pin "A") (pinfunction "A_A") (pintype "passive"))
    )
    (net (code "16") (name "A_7") (class "Default")
      (node (ref "IC3") (pin "3") (pinfunction "Q1_3") (pintype "tri_state"))
      (node (ref "IC4") (pin "2") (pinfunction "A1_2") (pintype "bidirectional"))
      (node (ref "IC6") (pin "12") (pinfunction "A4_12") (pintype "input"))
      (node (ref "LED9") (pin "A") (pinfunction "A_A") (pintype "passive"))
    )
    (net (code "17") (name "A_BUS_0") (class "Default")
      (node (ref "IC2") (pin "11") (pinfunction "D4_11") (pintype "input"))
      (node (ref "IC4") (pin "11") (pinfunction "B8_11") (pintype "bidirectional"))
      (node (ref "JP3") (pin "1") (pinfunction "1_1") (pintype "passive"))
    )
    (net (code "18") (name "A_BUS_1") (class "Default")
      (node (ref "IC2") (pin "12") (pinfunction "D3_12") (pintype "input"))
      (node (ref "IC4") (pin "12") (pinfunction "B7_12") (pintype "bidirectional"))
      (node (ref "JP3") (pin "2") (pinfunction "2_2") (pintype "passive"))
    )
    (net (code "19") (name "A_BUS_2") (class "Default")
      (node (ref "IC2") (pin "13") (pinfunction "D2_13") (pintype "input"))
      (node (ref "IC4") (pin "13") (pinfunction "B6_13") (pintype "bidirectional"))
      (node (ref "JP3") (pin "3") (pinfunction "3_3") (pintype "passive"))
    )
    (net (code "20") (name "A_BUS_3") (class "Default")
      (node (ref "IC2") (pin "14") (pinfunction "D1_14") (pintype "input"))
      (node (ref "IC4") (pin "14") (pinfunction "B5_14") (pintype "bidirectional"))
      (node (ref "JP3") (pin "4") (pinfunction "4_4") (pintype "passive"))
    )
    (net (code "21") (name "A_BUS_4") (class "Default")
      (node (ref "IC3") (pin "11") (pinfunction "D4_11") (pintype "input"))
      (node (ref "IC4") (pin "15") (pinfunction "B4_15") (pintype "bidirectional"))
      (node (ref "JP3") (pin "5") (pinfunction "5_5") (pintype "passive"))
    )
    (net (code "22") (name "A_BUS_5") (class "Default")
      (node (ref "IC3") (pin "12") (pinfunction "D3_12") (pintype "input"))
      (node (ref "IC4") (pin "16") (pinfunction "B3_16") (pintype "bidirectional"))
      (node (ref "JP3") (pin "6") (pinfunction "6_6") (pintype "passive"))
    )
    (net (code "23") (name "A_BUS_6") (class "Default")
      (node (ref "IC3") (pin "13") (pinfunction "D2_13") (pintype "input"))
      (node (ref "IC4") (pin "17") (pinfunction "B2_17") (pintype "bidirectional"))
      (node (ref "JP3") (pin "7") (pinfunction "7_7") (pintype "passive"))
    )
    (net (code "24") (name "A_BUS_7") (class "Default")
      (node (ref "IC3") (pin "14") (pinfunction "D1_14") (pintype "input"))
      (node (ref "IC4") (pin "18") (pinfunction "B1_18") (pintype "bidirectional"))
      (node (ref "JP3") (pin "8") (pinfunction "8_8") (pintype "passive"))
    )
    (net (code "25") (name "B_0") (class "Default")
      (node (ref "IC10") (pin "12") (pinfunction "I0_12") (pintype "input"))
      (node (ref "IC13") (pin "6") (pinfunction "Q4_6") (pintype "tri_state"))
      (node (ref "IC15") (pin "9") (pinfunction "A8_9") (pintype "bidirectional"))
      (node (ref "LED26") (pin "A") (pinfunction "A_A") (pintype "passive"))
    )
    (net (code "26") (name "B_1") (class "Default")
      (node (ref "IC10") (pin "9") (pinfunction "I0_9") (pintype "input"))
      (node (ref "IC13") (pin "5") (pinfunction "Q3_5") (pintype "tri_state"))
      (node (ref "IC15") (pin "8") (pinfunction "A7_8") (pintype "bidirectional"))
      (node (ref "LED25") (pin "A") (pinfunction "A_A") (pintype "passive"))
    )
    (net (code "27") (name "B_2") (class "Default")
      (node (ref "IC10") (pin "4") (pinfunction "I0_4") (pintype "input"))
      (node (ref "IC13") (pin "4") (pinfunction "Q2_4") (pintype "tri_state"))
      (node (ref "IC15") (pin "7") (pinfunction "A6_7") (pintype "bidirectional"))
      (node (ref "LED24") (pin "A") (pinfunction "A_A") (pintype "passive"))
    )
    (net (code "28") (name "B_3") (class "Default")
      (node (ref "IC10") (pin "1") (pinfunction "I0_1") (pintype "input"))
      (node (ref "IC13") (pin "3") (pinfunction "Q1_3") (pintype "tri_state"))
      (node (ref "IC15") (pin "6") (pinfunction "A5_6") (pintype "bidirectional"))
      (node (ref "LED23") (pin "A") (pinfunction "A_A") (pintype "passive"))
    )
    (net (code "29") (name "B_4") (class "Default")
      (node (ref "IC14") (pin "6") (pinfunction "Q4_6") (pintype "tri_state"))
      (node (ref "IC15") (pin "5") (pinfunction "A4_5") (pintype "bidirectional"))
      (node (ref "IC9") (pin "12") (pinfunction "I0_12") (pintype "input"))
      (node (ref "LED30") (pin "A") (pinfunction "A_A") (pintype "passive"))
    )
    (net (code "30") (name "B_5") (class "Default")
      (node (ref "IC14") (pin "5") (pinfunction "Q3_5") (pintype "tri_state"))
      (node (ref "IC15") (pin "4") (pinfunction "A3_4") (pintype "bidirectional"))
      (node (ref "IC9") (pin "9") (pinfunction "I0_9") (pintype "input"))
      (node (ref "LED29") (pin "A") (pinfunction "A_A") (pintype "passive"))
    )
    (net (code "31") (name "B_6") (class "Default")
      (node (ref "IC14") (pin "4") (pinfunction "Q2_4") (pintype "tri_state"))
      (node (ref "IC15") (pin "3") (pinfunction "A2_3") (pintype "bidirectional"))
      (node (ref "IC9") (pin "4") (pinfunction "I0_4") (pintype "input"))
      (node (ref "LED28") (pin "A") (pinfunction "A_A") (pintype "passive"))
    )
    (net (code "32") (name "B_7") (class "Default")
      (node (ref "IC14") (pin "3") (pinfunction "Q1_3") (pintype "tri_state"))
      (node (ref "IC15") (pin "2") (pinfunction "A1_2") (pintype "bidirectional"))
      (node (ref "IC9") (pin "1") (pinfunction "I0_1") (pintype "input"))
      (node (ref "LED27") (pin "A") (pinfunction "A_A") (pintype "passive"))
    )
    (net (code "33") (name "B_BUS_0") (class "Default")
      (node (ref "IC13") (pin "11") (pinfunction "D4_11") (pintype "input"))
      (node (ref "IC15") (pin "11") (pinfunction "B8_11") (pintype "bidirectional"))
      (node (ref "JP7") (pin "1") (pinfunction "1_1") (pintype "passive"))
    )
    (net (code "34") (name "B_BUS_1") (class "Default")
      (node (ref "IC13") (pin "12") (pinfunction "D3_12") (pintype "input"))
      (node (ref "IC15") (pin "12") (pinfunction "B7_12") (pintype "bidirectional"))
      (node (ref "JP7") (pin "2") (pinfunction "2_2") (pintype "passive"))
    )
    (net (code "35") (name "B_BUS_2") (class "Default")
      (node (ref "IC13") (pin "13") (pinfunction "D2_13") (pintype "input"))
      (node (ref "IC15") (pin "13") (pinfunction "B6_13") (pintype "bidirectional"))
      (node (ref "JP7") (pin "3") (pinfunction "3_3") (pintype "passive"))
    )
    (net (code "36") (name "B_BUS_3") (class "Default")
      (node (ref "IC13") (pin "14") (pinfunction "D1_14") (pintype "input"))
      (node (ref "IC15") (pin "14") (pinfunction "B5_14") (pintype "bidirectional"))
      (node (ref "JP7") (pin "4") (pinfunction "4_4") (pintype "passive"))
    )
    (net (code "37") (name "B_BUS_4") (class "Default")
      (node (ref "IC14") (pin "11") (pinfunction "D4_11") (pintype "input"))
      (node (ref "IC15") (pin "15") (pinfunction "B4_15") (pintype "bidirectional"))
      (node (ref "JP7") (pin "5") (pinfunction "5_5") (pintype "passive"))
    )
    (net (code "38") (name "B_BUS_5") (class "Default")
      (node (ref "IC14") (pin "12") (pinfunction "D3_12") (pintype "input"))
      (node (ref "IC15") (pin "16") (pinfunction "B3_16") (pintype "bidirectional"))
      (node (ref "JP7") (pin "6") (pinfunction "6_6") (pintype "passive"))
    )
    (net (code "39") (name "B_BUS_6") (class "Default")
      (node (ref "IC14") (pin "13") (pinfunction "D2_13") (pintype "input"))
      (node (ref "IC15") (pin "17") (pinfunction "B2_17") (pintype "bidirectional"))
      (node (ref "JP7") (pin "7") (pinfunction "7_7") (pintype "passive"))
    )
    (net (code "40") (name "B_BUS_7") (class "Default")
      (node (ref "IC14") (pin "14") (pinfunction "D1_14") (pintype "input"))
      (node (ref "IC15") (pin "18") (pinfunction "B1_18") (pintype "bidirectional"))
      (node (ref "JP7") (pin "8") (pinfunction "8_8") (pintype "passive"))
    )
    (net (code "41") (name "CE") (class "Default")
      (node (ref "JP6") (pin "1") (pinfunction "1_1") (pintype "passive"))
      (node (ref "U2") (pin "10") (pinfunction "ENT_10") (pintype "input"))
      (node (ref "U2") (pin "7") (pinfunction "ENP_7") (pintype "input"))
    )
    (net (code "42") (name "CF") (class "Default")
      (node (ref "IC8") (pin "3") (pinfunction "Q1_3") (pintype "tri_state"))
      (node (ref "JP6") (pin "5") (pinfunction "5_5") (pintype "passive"))
      (node (ref "LED21") (pin "A") (pinfunction "A_A") (pintype "passive"))
    )
    (net (code "43") (name "CLK") (class "Default")
      (node (ref "IC13") (pin "7") (pinfunction "CLK_7") (pintype "input"))
      (node (ref "IC14") (pin "7") (pinfunction "CLK_7") (pintype "input"))
      (node (ref "IC2") (pin "7") (pinfunction "CLK_7") (pintype "input"))
      (node (ref "IC21") (pin "2") (pinfunction "I1_2") (pintype "input"))
      (node (ref "IC3") (pin "7") (pinfunction "CLK_7") (pintype "input"))
      (node (ref "IC8") (pin "7") (pinfunction "CLK_7") (pintype "input"))
      (node (ref "JP6") (pin "2") (pinfunction "2_2") (pintype "passive"))
      (node (ref "U2") (pin "2") (pinfunction "CLK_2") (pintype "input"))
    )
    (net (code "44") (name "CLR") (class "Default")
      (node (ref "IC13") (pin "15") (pinfunction "CLR_15") (pintype "input"))
      (node (ref "IC14") (pin "15") (pinfunction "CLR_15") (pintype "input"))
      (node (ref "IC2") (pin "15") (pinfunction "CLR_15") (pintype "input"))
      (node (ref "IC3") (pin "15") (pinfunction "CLR_15") (pintype "input"))
      (node (ref "IC8") (pin "15") (pinfunction "CLR_15") (pintype "input"))
    )
    (net (code "45") (name "GND") (class "Default")
      (node (ref "C1") (pin "2") (pinfunction "2_2") (pintype "passive"))
      (node (ref "C2") (pin "2") (pinfunction "2_2") (pintype "passive"))
      (node (ref "C3") (pin "2") (pinfunction "2_2") (pintype "passive"))
      (node (ref "C4") (pin "2") (pinfunction "2_2") (pintype "passive"))
      (node (ref "C5") (pin "2") (pinfunction "2_2") (pintype "passive"))
      (node (ref "C6") (pin "2") (pinfunction "2_2") (pintype "passive"))
      (node (ref "C7") (pin "2") (pinfunction "2_2") (pintype "passive"))
      (node (ref "C8") (pin "2") (pinfunction "2_2") (pintype "passive"))
      (node (ref "C9") (pin "2") (pinfunction "2_2") (pintype "passive"))
      (node (ref "D1") (pin "A") (pinfunction "A_A") (pintype "passive"))
      (node (ref "IC1") (pin "1") (pinfunction "DIR_1") (pintype "input"))
      (node (ref "IC13") (pin "1") (pinfunction "M_1") (pintype "input"))
      (node (ref "IC13") (pin "2") (pinfunction "N_2") (pintype "input"))
      (node (ref "IC14") (pin "1") (pinfunction "M_1") (pintype "input"))
      (node (ref "IC14") (pin "2") (pinfunction "N_2") (pintype "input"))
      (node (ref "IC16") (pin "1") (pinfunction "G_1") (pintype "input"))
      (node (ref "IC17") (pin "12") (pinfunction "GND_12") (pintype "power_in"))
      (node (ref "IC17") (pin "18") (pinfunction "~{CE}_18") (pintype "input"))
      (node (ref "IC17") (pin "20") (pinfunction "~{OE}_20") (pintype "input"))
      (node (ref "IC19") (pin "1") (pinfunction "GND_1") (pintype "power_in"))
      (node (ref "IC2") (pin "1") (pinfunction "M_1") (pintype "input"))
      (node (ref "IC2") (pin "2") (pinfunction "N_2") (pintype "input"))
      (node (ref "IC3") (pin "1") (pinfunction "M_1") (pintype "input"))
      (node (ref "IC3") (pin "2") (pinfunction "N_2") (pintype "input"))
      (node (ref "IC8") (pin "1") (pinfunction "M_1") (pintype "input"))
      (node (ref "IC8") (pin "2") (pinfunction "N_2") (pintype "input"))
      (node (ref "J1") (pin "2") (pinfunction "2_2") (pintype "passive"))
      (node (ref "J1") (pin "3") (pinfunction "3_3") (pintype "passive"))
      (node (ref "JP1") (pin "3") (pinfunction "3_3") (pintype "passive"))
      (node (ref "JP1") (pin "4") (pinfunction "4_4") (pintype "passive"))
      (node (ref "Q1") (pin "G") (pinfunction "G_G") (pintype "passive"))
      (node (ref "R1") (pin "2") (pinfunction "2_2") (pintype "passive"))
      (node (ref "R10") (pin "1") (pinfunction "1_1") (pintype "passive"))
      (node (ref "R11") (pin "1") (pinfunction "1_1") (pintype "passive"))
      (node (ref "R12") (pin "1") (pinfunction "1_1") (pintype "passive"))
      (node (ref "R13") (pin "2") (pinfunction "2_2") (pintype "passive"))
      (node (ref "R14") (pin "2") (pinfunction "2_2") (pintype "passive"))
      (node (ref "R15") (pin "2") (pinfunction "2_2") (pintype "passive"))
      (node (ref "R16") (pin "2") (pinfunction "2_2") (pintype "passive"))
      (node (ref "R17") (pin "2") (pinfunction "2_2") (pintype "passive"))
      (node (ref "R18") (pin "2") (pinfunction "2_2") (pintype "passive"))
      (node (ref "R19") (pin "2") (pinfunction "2_2") (pintype "passive"))
      (node (ref "R2") (pin "2") (pinfunction "2_2") (pintype "passive"))
      (node (ref "R20") (pin "2") (pinfunction "2_2") (pintype "passive"))
      (node (ref "R21") (pin "2") (pinfunction "2_2") (pintype "passive"))
      (node (ref "R22") (pin "2") (pinfunction "2_2") (pintype "passive"))
      (node (ref "R23") (pin "1") (pinfunction "1_1") (pintype "passive"))
      (node (ref "R24") (pin "1") (pinfunction "1_1") (pintype "passive"))
      (node (ref "R25") (pin "1") (pinfunction "1_1") (pintype "passive"))
      (node (ref "R26") (pin "1") (pinfunction "1_1") (pintype "passive"))
      (node (ref "R27") (pin "1") (pinfunction "1_1") (pintype "passive"))
      (node (ref "R28") (pin "1") (pinfunction "1_1") (pintype "passive"))
      (node (ref "R29") (pin "1") (pinfunction "1_1") (pintype "passive"))
      (node (ref "R3") (pin "2") (pinfunction "2_2") (pintype "passive"))
      (node (ref "R30") (pin "1") (pinfunction "1_1") (pintype "passive"))
      (node (ref "R33") (pin "1") (pinfunction "1_1") (pintype "passive"))
      (node (ref "R35") (pin "1") (pinfunction "1_1") (pintype "passive"))
      (node (ref "R4") (pin "2") (pinfunction "2_2") (pintype "passive"))
      (node (ref "R5") (pin "1") (pinfunction "1_1") (pintype "passive"))
      (node (ref "R6") (pin "1") (pinfunction "1_1") (pintype "passive"))
      (node (ref "R7") (pin "1") (pinfunction "1_1") (pintype "passive"))
      (node (ref "R8") (pin "1") (pinfunction "1_1") (pintype "passive"))
      (node (ref "R9") (pin "1") (pinfunction "1_1") (pintype "passive"))
    )
    (net (code "46") (name "N_AI") (class "Default")
      (node (ref "IC2") (pin "10") (pinfunction "G2_10") (pintype "input"))
      (node (ref "IC2") (pin "9") (pinfunction "G1_9") (pintype "input"))
      (node (ref "IC3") (pin "10") (pinfunction "G2_10") (pintype "input"))
      (node (ref "IC3") (pin "9") (pinfunction "G1_9") (pintype "input"))
      (node (ref "JP6") (pin "10") (pinfunction "10_10") (pintype "passive"))
    )
    (net (code "47") (name "N_AO") (class "Default")
      (node (ref "IC4") (pin "19") (pinfunction "G_19") (pintype "input"))
      (node (ref "JP6") (pin "11") (pinfunction "11_11") (pintype "passive"))
    )
    (net (code "48") (name "N_BI") (class "Default")
      (node (ref "IC13") (pin "10") (pinfunction "G2_10") (pintype "input"))
      (node (ref "IC13") (pin "9") (pinfunction "G1_9") (pintype "input"))
      (node (ref "IC14") (pin "10") (pinfunction "G2_10") (pintype "input"))
      (node (ref "IC14") (pin "9") (pinfunction "G1_9") (pintype "input"))
      (node (ref "JP6") (pin "13") (pinfunction "13_13") (pintype "passive"))
    )
    (net (code "49") (name "N_BO") (class "Default")
      (node (ref "IC15") (pin "19") (pinfunction "G_19") (pintype "input"))
    )
    (net (code "50") (name "N_CLR") (class "Default")
      (node (ref "IC20") (pin "1") (pinfunction "CLR_1") (pintype "input"))
      (node (ref "JP6") (pin "8") (pinfunction "8_8") (pintype "passive"))
      (node (ref "U2") (pin "1") (pinfunction "CLR_1") (pintype "input"))
    )
    (net (code "51") (name "N_CO") (class "Default")
      (node (ref "IC1") (pin "19") (pinfunction "G_19") (pintype "input"))
      (node (ref "JP6") (pin "14") (pinfunction "14_14") (pintype "passive"))
    )
    (net (code "52") (name "N_EO") (class "Default")
      (node (ref "IC7") (pin "19") (pinfunction "G_19") (pintype "input"))
      (node (ref "JP6") (pin "12") (pinfunction "12_12") (pintype "passive"))
    )
    (net (code "53") (name "N_FI") (class "Default")
      (node (ref "IC8") (pin "10") (pinfunction "G2_10") (pintype "input"))
      (node (ref "IC8") (pin "9") (pinfunction "G1_9") (pintype "input"))
      (node (ref "JP6") (pin "7") (pinfunction "7_7") (pintype "passive"))
    )
    (net (code "54") (name "N_J") (class "Default")
      (node (ref "JP6") (pin "9") (pinfunction "9_9") (pintype "passive"))
      (node (ref "U2") (pin "9") (pinfunction "LD_9") (pintype "input"))
    )
    (net (code "55") (name "Net-(D1-PadC)") (class "Default")
      (node (ref "D1") (pin "C") (pinfunction "C_C") (pintype "passive"))
      (node (ref "Q2") (pin "G") (pinfunction "G_G") (pintype "passive"))
      (node (ref "R34") (pin "1") (pinfunction "1_1") (pintype "passive"))
    )
    (net (code "56") (name "Net-(DIS5-A)") (class "Default")
      (node (ref "DIS5") (pin "7") (pinfunction "A_7") (pintype "passive"))
      (node (ref "DIS6") (pin "7") (pinfunction "A_7") (pintype "passive"))
      (node (ref "DIS7") (pin "7") (pinfunction "A_7") (pintype "passive"))
      (node (ref "DIS8") (pin "7") (pinfunction "A_7") (pintype "passive"))
      (node (ref "IC17") (pin "16") (pinfunction "D6_16") (pintype "tri_state"))
    )
    (net (code "57") (name "Net-(DIS5-B)") (class "Default")
      (node (ref "DIS5") (pin "6") (pinfunction "B_6") (pintype "passive"))
      (node (ref "DIS6") (pin "6") (pinfunction "B_6") (pintype "passive"))
      (node (ref "DIS7") (pin "6") (pinfunction "B_6") (pintype "passive"))
      (node (ref "DIS8") (pin "6") (pinfunction "B_6") (pintype "passive"))
      (node (ref "IC17") (pin "15") (pinfunction "D5_15") (pintype "tri_state"))
    )
    (net (code "58") (name "Net-(DIS5-C)") (class "Default")
      (node (ref "DIS5") (pin "4") (pinfunction "C_4") (pintype "passive"))
      (node (ref "DIS6") (pin "4") (pinfunction "C_4") (pintype "passive"))
      (node (ref "DIS7") (pin "4") (pinfunction "C_4") (pintype "passive"))
      (node (ref "DIS8") (pin "4") (pinfunction "C_4") (pintype "passive"))
      (node (ref "IC17") (pin "14") (pinfunction "D4_14") (pintype "tri_state"))
    )
    (net (code "59") (name "Net-(DIS5-D)") (class "Default")
      (node (ref "DIS5") (pin "2") (pinfunction "D_2") (pintype "passive"))
      (node (ref "DIS6") (pin "2") (pinfunction "D_2") (pintype "passive"))
      (node (ref "DIS7") (pin "2") (pinfunction "D_2") (pintype "passive"))
      (node (ref "DIS8") (pin "2") (pinfunction "D_2") (pintype "passive"))
      (node (ref "IC17") (pin "13") (pinfunction "D3_13") (pintype "tri_state"))
    )
    (net (code "60") (name "Net-(DIS5-DP)") (class "Default")
      (node (ref "DIS5") (pin "5") (pinfunction "DP_5") (pintype "passive"))
      (node (ref "DIS6") (pin "5") (pinfunction "DP_5") (pintype "passive"))
      (node (ref "DIS7") (pin "5") (pinfunction "DP_5") (pintype "passive"))
      (node (ref "DIS8") (pin "5") (pinfunction "DP_5") (pintype "passive"))
      (node (ref "IC17") (pin "17") (pinfunction "D7_17") (pintype "tri_state"))
    )
    (net (code "61") (name "Net-(DIS5-E)") (class "Default")
      (node (ref "DIS5") (pin "1") (pinfunction "E_1") (pintype "passive"))
      (node (ref "DIS6") (pin "1") (pinfunction "E_1") (pintype "passive"))
      (node (ref "DIS7") (pin "1") (pinfunction "E_1") (pintype "passive"))
      (node (ref "DIS8") (pin "1") (pinfunction "E_1") (pintype "passive"))
      (node (ref "IC17") (pin "11") (pinfunction "D2_11") (pintype "tri_state"))
    )
    (net (code "62") (name "Net-(DIS5-F)") (class "Default")
      (node (ref "DIS5") (pin "9") (pinfunction "F_9") (pintype "passive"))
      (node (ref "DIS6") (pin "9") (pinfunction "F_9") (pintype "passive"))
      (node (ref "DIS7") (pin "9") (pinfunction "F_9") (pintype "passive"))
      (node (ref "DIS8") (pin "9") (pinfunction "F_9") (pintype "passive"))
      (node (ref "IC17") (pin "10") (pinfunction "D1_10") (pintype "tri_state"))
    )
    (net (code "63") (name "Net-(DIS5-G)") (class "Default")
      (node (ref "DIS5") (pin "10") (pinfunction "G_10") (pintype "passive"))
      (node (ref "DIS6") (pin "10") (pinfunction "G_10") (pintype "passive"))
      (node (ref "DIS7") (pin "10") (pinfunction "G_10") (pintype "passive"))
      (node (ref "DIS8") (pin "10") (pinfunction "G_10") (pintype "passive"))
      (node (ref "IC17") (pin "9") (pinfunction "D0_9") (pintype "tri_state"))
    )
    (net (code "64") (name "Net-(IC1A-B5)") (class "Default")
      (node (ref "IC1") (pin "14") (pinfunction "B5_14") (pintype "bidirectional"))
      (node (ref "LED1") (pin "A") (pinfunction "A_A") (pintype "passive"))
      (node (ref "U2") (pin "11") (pinfunction "QD_11") (pintype "output"))
    )
    (net (code "65") (name "Net-(IC1A-B6)") (class "Default")
      (node (ref "IC1") (pin "13") (pinfunction "B6_13") (pintype "bidirectional"))
      (node (ref "LED2") (pin "A") (pinfunction "A_A") (pintype "passive"))
      (node (ref "U2") (pin "12") (pinfunction "QC_12") (pintype "output"))
    )
    (net (code "66") (name "Net-(IC1A-B7)") (class "Default")
      (node (ref "IC1") (pin "12") (pinfunction "B7_12") (pintype "bidirectional"))
      (node (ref "LED3") (pin "A") (pinfunction "A_A") (pintype "passive"))
      (node (ref "U2") (pin "13") (pinfunction "QB_13") (pintype "output"))
    )
    (net (code "67") (name "Net-(IC1A-B8)") (class "Default")
      (node (ref "IC1") (pin "11") (pinfunction "B8_11") (pintype "bidirectional"))
      (node (ref "LED4") (pin "A") (pinfunction "A_A") (pintype "passive"))
      (node (ref "U2") (pin "14") (pinfunction "QA_14") (pintype "output"))
    )
    (net (code "68") (name "Net-(IC5A-C4)") (class "Default")
      (node (ref "IC5") (pin "9") (pinfunction "C4_9") (pintype "output"))
      (node (ref "IC6") (pin "7") (pinfunction "C0_7") (pintype "input"))
    )
    (net (code "69") (name "Net-(IC6A-B1)") (class "Default")
      (node (ref "IC6") (pin "6") (pinfunction "B1_6") (pintype "input"))
      (node (ref "IC9") (pin "11") (pinfunction "O_11") (pintype "output"))
    )
    (net (code "70") (name "Net-(IC6A-B2)") (class "Default")
      (node (ref "IC6") (pin "2") (pinfunction "B2_2") (pintype "input"))
      (node (ref "IC9") (pin "8") (pinfunction "O_8") (pintype "output"))
    )
    (net (code "71") (name "Net-(IC6A-B3)") (class "Default")
      (node (ref "IC6") (pin "15") (pinfunction "B3_15") (pintype "input"))
      (node (ref "IC9") (pin "6") (pinfunction "O_6") (pintype "output"))
    )
    (net (code "72") (name "Net-(IC6A-B4)") (class "Default")
      (node (ref "IC6") (pin "11") (pinfunction "B4_11") (pintype "input"))
      (node (ref "IC9") (pin "3") (pinfunction "O_3") (pintype "output"))
    )
    (net (code "73") (name "Net-(IC6A-C4)") (class "Default")
      (node (ref "IC6") (pin "9") (pinfunction "C4_9") (pintype "output"))
      (node (ref "IC8") (pin "14") (pinfunction "D1_14") (pintype "input"))
    )
    (net (code "74") (name "Net-(IC10A-O)") (class "Default")
      (node (ref "IC10") (pin "3") (pinfunction "O_3") (pintype "output"))
      (node (ref "IC5") (pin "11") (pinfunction "B4_11") (pintype "input"))
    )
    (net (code "75") (name "Net-(IC10B-O)") (class "Default")
      (node (ref "IC10") (pin "6") (pinfunction "O_6") (pintype "output"))
      (node (ref "IC5") (pin "15") (pinfunction "B3_15") (pintype "input"))
    )
    (net (code "76") (name "Net-(IC10C-O)") (class "Default")
      (node (ref "IC10") (pin "8") (pinfunction "O_8") (pintype "output"))
      (node (ref "IC5") (pin "2") (pinfunction "B2_2") (pintype "input"))
    )
    (net (code "77") (name "Net-(IC10D-O)") (class "Default")
      (node (ref "IC10") (pin "11") (pinfunction "O_11") (pintype "output"))
      (node (ref "IC5") (pin "6") (pinfunction "B1_6") (pintype "input"))
    )
    (net (code "78") (name "Net-(IC11A-I0)") (class "Default")
      (node (ref "IC11") (pin "2") (pinfunction "I0_2") (pintype "input"))
      (node (ref "IC6") (pin "13") (pinfunction "S3_13") (pintype "output"))
      (node (ref "IC7") (pin "3") (pinfunction "A2_3") (pintype "bidirectional"))
      (node (ref "LED13") (pin "A") (pinfunction "A_A") (pintype "passive"))
    )
    (net (code "79") (name "Net-(IC11A-I1)") (class "Default")
      (node (ref "IC11") (pin "3") (pinfunction "I1_3") (pintype "input"))
      (node (ref "IC6") (pin "10") (pinfunction "S4_10") (pintype "output"))
      (node (ref "IC7") (pin "2") (pinfunction "A1_2") (pintype "bidirectional"))
      (node (ref "LED16") (pin "A") (pinfunction "A_A") (pintype "passive"))
    )
    (net (code "80") (name "Net-(IC11A-O)") (class "Default")
      (node (ref "IC11") (pin "1") (pinfunction "O_1") (pintype "output"))
      (node (ref "IC12") (pin "10") (pinfunction "I1_10") (pintype "input"))
    )
    (net (code "81") (name "Net-(IC11B-I0)") (class "Default")
      (node (ref "IC11") (pin "5") (pinfunction "I0_5") (pintype "input"))
      (node (ref "IC6") (pin "4") (pinfunction "S1_4") (pintype "output"))
      (node (ref "IC7") (pin "5") (pinfunction "A4_5") (pintype "bidirectional"))
      (node (ref "LED15") (pin "A") (pinfunction "A_A") (pintype "passive"))
    )
    (net (code "82") (name "Net-(IC11B-I1)") (class "Default")
      (node (ref "IC11") (pin "6") (pinfunction "I1_6") (pintype "input"))
      (node (ref "IC6") (pin "1") (pinfunction "S2_1") (pintype "output"))
      (node (ref "IC7") (pin "4") (pinfunction "A3_4") (pintype "bidirectional"))
      (node (ref "LED14") (pin "A") (pinfunction "A_A") (pintype "passive"))
    )
    (net (code "83") (name "Net-(IC11B-O)") (class "Default")
      (node (ref "IC11") (pin "4") (pinfunction "O_4") (pintype "output"))
      (node (ref "IC12") (pin "9") (pinfunction "I0_9") (pintype "input"))
    )
    (net (code "84") (name "Net-(IC11C-I0)") (class "Default")
      (node (ref "IC11") (pin "8") (pinfunction "I0_8") (pintype "input"))
      (node (ref "IC5") (pin "13") (pinfunction "S3_13") (pintype "output"))
      (node (ref "IC7") (pin "7") (pinfunction "A6_7") (pintype "bidirectional"))
      (node (ref "LED18") (pin "A") (pinfunction "A_A") (pintype "passive"))
    )
    (net (code "85") (name "Net-(IC11C-I1)") (class "Default")
      (node (ref "IC11") (pin "9") (pinfunction "I1_9") (pintype "input"))
      (node (ref "IC5") (pin "10") (pinfunction "S4_10") (pintype "output"))
      (node (ref "IC7") (pin "6") (pinfunction "A5_6") (pintype "bidirectional"))
      (node (ref "LED17") (pin "A") (pinfunction "A_A") (pintype "passive"))
    )
    (net (code "86") (name "Net-(IC11C-O)") (class "Default")
      (node (ref "IC11") (pin "10") (pinfunction "O_10") (pintype "output"))
      (node (ref "IC12") (pin "5") (pinfunction "I1_5") (pintype "input"))
    )
    (net (code "87") (name "Net-(IC11D-I0)") (class "Default")
      (node (ref "IC11") (pin "11") (pinfunction "I0_11") (pintype "input"))
      (node (ref "IC5") (pin "4") (pinfunction "S1_4") (pintype "output"))
      (node (ref "IC7") (pin "9") (pinfunction "A8_9") (pintype "bidirectional"))
      (node (ref "LED20") (pin "A") (pinfunction "A_A") (pintype "passive"))
    )
    (net (code "88") (name "Net-(IC11D-I1)") (class "Default")
      (node (ref "IC11") (pin "12") (pinfunction "I1_12") (pintype "input"))
      (node (ref "IC5") (pin "1") (pinfunction "S2_1") (pintype "output"))
      (node (ref "IC7") (pin "8") (pinfunction "A7_8") (pintype "bidirectional"))
      (node (ref "LED19") (pin "A") (pinfunction "A_A") (pintype "passive"))
    )
    (net (code "89") (name "Net-(IC11D-O)") (class "Default")
      (node (ref "IC11") (pin "13") (pinfunction "O_13") (pintype "output"))
      (node (ref "IC12") (pin "4") (pinfunction "I0_4") (pintype "input"))
    )
    (net (code "90") (name "Net-(IC12A-I0)") (class "Default")
      (node (ref "IC12") (pin "1") (pinfunction "I0_1") (pintype "input"))
      (node (ref "IC12") (pin "6") (pinfunction "O_6") (pintype "output"))
    )
    (net (code "91") (name "Net-(IC12A-I1)") (class "Default")
      (node (ref "IC12") (pin "2") (pinfunction "I1_2") (pintype "input"))
      (node (ref "IC12") (pin "8") (pinfunction "O_8") (pintype "output"))
    )
    (net (code "92") (name "Net-(IC12A-O)") (class "Default")
      (node (ref "IC12") (pin "3") (pinfunction "O_3") (pintype "output"))
      (node (ref "IC8") (pin "13") (pinfunction "D2_13") (pintype "input"))
    )
    (net (code "93") (name "Net-(IC16A-A)") (class "Default")
      (node (ref "IC16") (pin "2") (pinfunction "A_2") (pintype "input"))
      (node (ref "IC17") (pin "23") (pinfunction "A8_23") (pintype "input"))
      (node (ref "IC18") (pin "14") (pinfunction "~{Q}_14") (pintype "output"))
      (node (ref "IC18") (pin "6") (pinfunction "CLK_6") (pintype "input"))
    )
    (net (code "94") (name "Net-(IC16A-B)") (class "Default")
      (node (ref "IC16") (pin "3") (pinfunction "B_3") (pintype "input"))
      (node (ref "IC17") (pin "22") (pinfunction "A9_22") (pintype "input"))
      (node (ref "IC18") (pin "10") (pinfunction "~{Q}_10") (pintype "output"))
    )
    (net (code "95") (name "Net-(IC16A-Y0)") (class "Default")
      (node (ref "DIS8") (pin "3") (pinfunction "CC_3") (pintype "passive"))
      (node (ref "DIS8") (pin "8") (pinfunction "CC_8") (pintype "passive"))
      (node (ref "IC16") (pin "4") (pinfunction "Y0_4") (pintype "output"))
    )
    (net (code "96") (name "Net-(IC16A-Y1)") (class "Default")
      (node (ref "DIS7") (pin "3") (pinfunction "CC_3") (pintype "passive"))
      (node (ref "DIS7") (pin "8") (pinfunction "CC_8") (pintype "passive"))
      (node (ref "IC16") (pin "5") (pinfunction "Y1_5") (pintype "output"))
    )
    (net (code "97") (name "Net-(IC16A-Y2)") (class "Default")
      (node (ref "DIS6") (pin "3") (pinfunction "CC_3") (pintype "passive"))
      (node (ref "DIS6") (pin "8") (pinfunction "CC_8") (pintype "passive"))
      (node (ref "IC16") (pin "6") (pinfunction "Y2_6") (pintype "output"))
    )
    (net (code "98") (name "Net-(IC16A-Y3)") (class "Default")
      (node (ref "DIS5") (pin "3") (pinfunction "CC_3") (pintype "passive"))
      (node (ref "DIS5") (pin "8") (pinfunction "CC_8") (pintype "passive"))
      (node (ref "IC16") (pin "7") (pinfunction "Y3_7") (pintype "output"))
    )
    (net (code "99") (name "Net-(IC17-A0)") (class "Default")
      (node (ref "IC17") (pin "8") (pinfunction "A0_8") (pintype "input"))
      (node (ref "IC20") (pin "2") (pinfunction "Q1_2") (pintype "output"))
    )
    (net (code "100") (name "Net-(IC17-A1)") (class "Default")
      (node (ref "IC17") (pin "7") (pinfunction "A1_7") (pintype "input"))
      (node (ref "IC20") (pin "5") (pinfunction "Q2_5") (pintype "output"))
    )
    (net (code "101") (name "Net-(IC17-A2)") (class "Default")
      (node (ref "IC17") (pin "6") (pinfunction "A2_6") (pintype "input"))
      (node (ref "IC20") (pin "6") (pinfunction "Q3_6") (pintype "output"))
    )
    (net (code "102") (name "Net-(IC17-A3)") (class "Default")
      (node (ref "IC17") (pin "5") (pinfunction "A3_5") (pintype "input"))
      (node (ref "IC20") (pin "9") (pinfunction "Q4_9") (pintype "output"))
    )
    (net (code "103") (name "Net-(IC17-A4)") (class "Default")
      (node (ref "IC17") (pin "4") (pinfunction "A4_4") (pintype "input"))
      (node (ref "IC20") (pin "12") (pinfunction "Q5_12") (pintype "output"))
    )
    (net (code "104") (name "Net-(IC17-A5)") (class "Default")
      (node (ref "IC17") (pin "3") (pinfunction "A5_3") (pintype "input"))
      (node (ref "IC20") (pin "15") (pinfunction "Q6_15") (pintype "output"))
    )
    (net (code "105") (name "Net-(IC17-A6)") (class "Default")
      (node (ref "IC17") (pin "2") (pinfunction "A6_2") (pintype "input"))
      (node (ref "IC20") (pin "16") (pinfunction "Q7_16") (pintype "output"))
    )
    (net (code "106") (name "Net-(IC17-A7)") (class "Default")
      (node (ref "IC17") (pin "1") (pinfunction "A7_1") (pintype "input"))
      (node (ref "IC20") (pin "19") (pinfunction "Q8_19") (pintype "output"))
    )
    (net (code "107") (name "Net-(IC17-A10)") (class "Default")
      (node (ref "IC17") (pin "19") (pinfunction "A10_19") (pintype "input"))
      (node (ref "S1") (pin "2") (pinfunction "P_2") (pintype "passive"))
    )
    (net (code "108") (name "Net-(IC18A-CLK)") (class "Default")
      (node (ref "IC18") (pin "1") (pinfunction "CLK_1") (pintype "input"))
      (node (ref "IC19") (pin "3") (pinfunction "Q_3") (pintype "output"))
    )
    (net (code "109") (name "Net-(IC19-CV)") (class "Default")
      (node (ref "C9") (pin "1") (pinfunction "1_1") (pintype "passive"))
      (node (ref "IC19") (pin "5") (pinfunction "CV_5") (pintype "input"))
    )
    (net (code "110") (name "Net-(IC19-DIS)") (class "Default")
      (node (ref "IC19") (pin "7") (pinfunction "DIS_7") (pintype "input"))
      (node (ref "R31") (pin "1") (pinfunction "1_1") (pintype "passive"))
      (node (ref "R32") (pin "2") (pinfunction "2_2") (pintype "passive"))
    )
    (net (code "111") (name "Net-(IC19-THR)") (class "Default")
      (node (ref "C8") (pin "1") (pinfunction "1_1") (pintype "passive"))
      (node (ref "IC19") (pin "2") (pinfunction "TR_2") (pintype "input"))
      (node (ref "IC19") (pin "6") (pinfunction "THR_6") (pintype "input"))
      (node (ref "R32") (pin "1") (pinfunction "1_1") (pintype "passive"))
    )
    (net (code "112") (name "Net-(IC20A-CLK)") (class "Default")
      (node (ref "IC20") (pin "11") (pinfunction "CLK_11") (pintype "input"))
      (node (ref "IC21") (pin "3") (pinfunction "O_3") (pintype "output"))
    )
    (net (code "113") (name "Net-(LED1-C)") (class "Default")
      (node (ref "LED1") (pin "K") (pinfunction "C_K") (pintype "passive"))
      (node (ref "R4") (pin "1") (pinfunction "1_1") (pintype "passive"))
    )
    (net (code "114") (name "Net-(LED2-C)") (class "Default")
      (node (ref "LED2") (pin "K") (pinfunction "C_K") (pintype "passive"))
      (node (ref "R1") (pin "1") (pinfunction "1_1") (pintype "passive"))
    )
    (net (code "115") (name "Net-(LED3-C)") (class "Default")
      (node (ref "LED3") (pin "K") (pinfunction "C_K") (pintype "passive"))
      (node (ref "R2") (pin "1") (pinfunction "1_1") (pintype "passive"))
    )
    (net (code "116") (name "Net-(LED4-C)") (class "Default")
      (node (ref "LED4") (pin "K") (pinfunction "C_K") (pintype "passive"))
      (node (ref "R3") (pin "1") (pinfunction "1_1") (pintype "passive"))
    )
    (net (code "117") (name "Net-(LED5-C)") (class "Default")
      (node (ref "LED5") (pin "K") (pinfunction "C_K") (pintype "passive"))
      (node (ref "R8") (pin "2") (pinfunction "2_2") (pintype "passive"))
    )
    (net (code "118") (name "Net-(LED6-C)") (class "Default")
      (node (ref "LED6") (pin "K") (pinfunction "C_K") (pintype "passive"))
      (node (ref "R7") (pin "2") (pinfunction "2_2") (pintype "passive"))
    )
    (net (code "119") (name "Net-(LED7-C)") (class "Default")
      (node (ref "LED7") (pin "K") (pinfunction "C_K") (pintype "passive"))
      (node (ref "R6") (pin "2") (pinfunction "2_2") (pintype "passive"))
    )
    (net (code "120") (name "Net-(LED8-C)") (class "Default")
      (node (ref "LED8") (pin "K") (pinfunction "C_K") (pintype "passive"))
      (node (ref "R5") (pin "2") (pinfunction "2_2") (pintype "passive"))
    )
    (net (code "121") (name "Net-(LED9-C)") (class "Default")
      (node (ref "LED9") (pin "K") (pinfunction "C_K") (pintype "passive"))
      (node (ref "R12") (pin "2") (pinfunction "2_2") (pintype "passive"))
    )
    (net (code "122") (name "Net-(LED10-C)") (class "Default")
      (node (ref "LED10") (pin "K") (pinfunction "C_K") (pintype "passive"))
      (node (ref "R11") (pin "2") (pinfunction "2_2") (pintype "passive"))
    )
    (net (code "123") (name "Net-(LED11-C)") (class "Default")
      (node (ref "LED11") (pin "K") (pinfunction "C_K") (pintype "passive"))
      (node (ref "R10") (pin "2") (pinfunction "2_2") (pintype "passive"))
    )
    (net (code "124") (name "Net-(LED12-C)") (class "Default")
      (node (ref "LED12") (pin "K") (pinfunction "C_K") (pintype "passive"))
      (node (ref "R9") (pin "2") (pinfunction "2_2") (pintype "passive"))
    )
    (net (code "125") (name "Net-(LED13-C)") (class "Default")
      (node (ref "LED13") (pin "K") (pinfunction "C_K") (pintype "passive"))
      (node (ref "R13") (pin "1") (pinfunction "1_1") (pintype "passive"))
    )
    (net (code "126") (name "Net-(LED14-C)") (class "Default")
      (node (ref "LED14") (pin "K") (pinfunction "C_K") (pintype "passive"))
      (node (ref "R14") (pin "1") (pinfunction "1_1") (pintype "passive"))
    )
    (net (code "127") (name "Net-(LED15-C)") (class "Default")
      (node (ref "LED15") (pin "K") (pinfunction "C_K") (pintype "passive"))
      (node (ref "R15") (pin "1") (pinfunction "1_1") (pintype "passive"))
    )
    (net (code "128") (name "Net-(LED16-C)") (class "Default")
      (node (ref "LED16") (pin "K") (pinfunction "C_K") (pintype "passive"))
      (node (ref "R16") (pin "1") (pinfunction "1_1") (pintype "passive"))
    )
    (net (code "129") (name "Net-(LED17-C)") (class "Default")
      (node (ref "LED17") (pin "K") (pinfunction "C_K") (pintype "passive"))
      (node (ref "R17") (pin "1") (pinfunction "1_1") (pintype "passive"))
    )
    (net (code "130") (name "Net-(LED18-C)") (class "Default")
      (node (ref "LED18") (pin "K") (pinfunction "C_K") (pintype "passive"))
      (node (ref "R18") (pin "1") (pinfunction "1_1") (pintype "passive"))
    )
    (net (code "131") (name "Net-(LED19-C)") (class "Default")
      (node (ref "LED19") (pin "K") (pinfunction "C_K") (pintype "passive"))
      (node (ref "R19") (pin "1") (pinfunction "1_1") (pintype "passive"))
    )
    (net (code "132") (name "Net-(LED20-C)") (class "Default")
      (node (ref "LED20") (pin "K") (pinfunction "C_K") (pintype "passive"))
      (node (ref "R20") (pin "1") (pinfunction "1_1") (pintype "passive"))
    )
    (net (code "133") (name "Net-(LED21-C)") (class "Default")
      (node (ref "LED21") (pin "K") (pinfunction "C_K") (pintype "passive"))
      (node (ref "R21") (pin "1") (pinfunction "1_1") (pintype "passive"))
    )
    (net (code "134") (name "Net-(LED22-C)") (class "Default")
      (node (ref "LED22") (pin "K") (pinfunction "C_K") (pintype "passive"))
      (node (ref "R22") (pin "1") (pinfunction "1_1") (pintype "passive"))
    )
    (net (code "135") (name "Net-(LED23-C)") (class "Default")
      (node (ref "LED23") (pin "K") (pinfunction "C_K") (pintype "passive"))
      (node (ref "R26") (pin "2") (pinfunction "2_2") (pintype "passive"))
    )
    (net (code "136") (name "Net-(LED24-C)") (class "Default")
      (node (ref "LED24") (pin "K") (pinfunction "C_K") (pintype "passive"))
      (node (ref "R25") (pin "2") (pinfunction "2_2") (pintype "passive"))
    )
    (net (code "137") (name "Net-(LED25-C)") (class "Default")
      (node (ref "LED25") (pin "K") (pinfunction "C_K") (pintype "passive"))
      (node (ref "R24") (pin "2") (pinfunction "2_2") (pintype "passive"))
    )
    (net (code "138") (name "Net-(LED26-C)") (class "Default")
      (node (ref "LED26") (pin "K") (pinfunction "C_K") (pintype "passive"))
      (node (ref "R23") (pin "2") (pinfunction "2_2") (pintype "passive"))
    )
    (net (code "139") (name "Net-(LED27-C)") (class "Default")
      (node (ref "LED27") (pin "K") (pinfunction "C_K") (pintype "passive"))
      (node (ref "R30") (pin "2") (pinfunction "2_2") (pintype "passive"))
    )
    (net (code "140") (name "Net-(LED28-C)") (class "Default")
      (node (ref "LED28") (pin "K") (pinfunction "C_K") (pintype "passive"))
      (node (ref "R29") (pin "2") (pinfunction "2_2") (pintype "passive"))
    )
    (net (code "141") (name "Net-(LED29-C)") (class "Default")
      (node (ref "LED29") (pin "K") (pinfunction "C_K") (pintype "passive"))
      (node (ref "R28") (pin "2") (pinfunction "2_2") (pintype "passive"))
    )
    (net (code "142") (name "Net-(LED30-C)") (class "Default")
      (node (ref "LED30") (pin "K") (pinfunction "C_K") (pintype "passive"))
      (node (ref "R27") (pin "2") (pinfunction "2_2") (pintype "passive"))
    )
    (net (code "143") (name "Net-(Q1-PadS)") (class "Default")
      (node (ref "Q1") (pin "S") (pinfunction "S_S") (pintype "passive"))
      (node (ref "Q2") (pin "S") (pinfunction "S_S") (pintype "passive"))
      (node (ref "Q3") (pin "S") (pinfunction "S_S") (pintype "passive"))
      (node (ref "R34") (pin "2") (pinfunction "2_2") (pintype "passive"))
    )
    (net (code "144") (name "Net-(Q2-PadD)") (class "Default")
      (node (ref "Q2") (pin "D") (pinfunction "D_D") (pintype "passive"))
      (node (ref "Q3") (pin "G") (pinfunction "G_G") (pintype "passive"))
      (node (ref "R35") (pin "2") (pinfunction "2_2") (pintype "passive"))
    )
    (net (code "145") (name "Net-(S1-O)") (class "Default")
      (node (ref "R33") (pin "2") (pinfunction "2_2") (pintype "passive"))
      (node (ref "S1") (pin "1") (pinfunction "O_1") (pintype "passive"))
    )
    (net (code "146") (name "Net-(S2-P)") (class "Default")
      (node (ref "Q3") (pin "D") (pinfunction "D_D") (pintype "passive"))
      (node (ref "S2") (pin "2") (pinfunction "P_2") (pintype "passive"))
    )
    (net (code "147") (name "OI") (class "Default")
      (node (ref "IC21") (pin "1") (pinfunction "I0_1") (pintype "input"))
      (node (ref "JP6") (pin "4") (pinfunction "4_4") (pintype "passive"))
    )
    (net (code "148") (name "OUT_BUS_0") (class "Default")
      (node (ref "IC20") (pin "3") (pinfunction "D1_3") (pintype "input"))
      (node (ref "JP4") (pin "1") (pinfunction "1_1") (pintype "passive"))
    )
    (net (code "149") (name "OUT_BUS_1") (class "Default")
      (node (ref "IC20") (pin "4") (pinfunction "D2_4") (pintype "input"))
      (node (ref "JP4") (pin "2") (pinfunction "2_2") (pintype "passive"))
    )
    (net (code "150") (name "OUT_BUS_2") (class "Default")
      (node (ref "IC20") (pin "7") (pinfunction "D3_7") (pintype "input"))
      (node (ref "JP4") (pin "3") (pinfunction "3_3") (pintype "passive"))
    )
    (net (code "151") (name "OUT_BUS_3") (class "Default")
      (node (ref "IC20") (pin "8") (pinfunction "D4_8") (pintype "input"))
      (node (ref "JP4") (pin "4") (pinfunction "4_4") (pintype "passive"))
    )
    (net (code "152") (name "OUT_BUS_4") (class "Default")
      (node (ref "IC20") (pin "13") (pinfunction "D5_13") (pintype "input"))
      (node (ref "JP4") (pin "5") (pinfunction "5_5") (pintype "passive"))
    )
    (net (code "153") (name "OUT_BUS_5") (class "Default")
      (node (ref "IC20") (pin "14") (pinfunction "D6_14") (pintype "input"))
      (node (ref "JP4") (pin "6") (pinfunction "6_6") (pintype "passive"))
    )
    (net (code "154") (name "OUT_BUS_6") (class "Default")
      (node (ref "IC20") (pin "17") (pinfunction "D7_17") (pintype "input"))
      (node (ref "JP4") (pin "7") (pinfunction "7_7") (pintype "passive"))
    )
    (net (code "155") (name "OUT_BUS_7") (class "Default")
      (node (ref "IC20") (pin "18") (pinfunction "D8_18") (pintype "input"))
      (node (ref "JP4") (pin "8") (pinfunction "8_8") (pintype "passive"))
    )
    (net (code "156") (name "PC_BUS_0") (class "Default")
      (node (ref "IC1") (pin "9") (pinfunction "A8_9") (pintype "bidirectional"))
      (node (ref "JP2") (pin "1") (pinfunction "1_1") (pintype "passive"))
      (node (ref "U2") (pin "3") (pinfunction "A_3") (pintype "input"))
    )
    (net (code "157") (name "PC_BUS_1") (class "Default")
      (node (ref "IC1") (pin "8") (pinfunction "A7_8") (pintype "bidirectional"))
      (node (ref "JP2") (pin "2") (pinfunction "2_2") (pintype "passive"))
      (node (ref "U2") (pin "4") (pinfunction "B_4") (pintype "input"))
    )
    (net (code "158") (name "PC_BUS_2") (class "Default")
      (node (ref "IC1") (pin "7") (pinfunction "A6_7") (pintype "bidirectional"))
      (node (ref "JP2") (pin "3") (pinfunction "3_3") (pintype "passive"))
      (node (ref "U2") (pin "5") (pinfunction "C_5") (pintype "input"))
    )
    (net (code "159") (name "PC_BUS_3") (class "Default")
      (node (ref "IC1") (pin "6") (pinfunction "A5_6") (pintype "bidirectional"))
      (node (ref "JP2") (pin "4") (pinfunction "4_4") (pintype "passive"))
      (node (ref "U2") (pin "6") (pinfunction "D_6") (pintype "input"))
    )
    (net (code "160") (name "SU") (class "Default")
      (node (ref "IC10") (pin "10") (pinfunction "I1_10") (pintype "input"))
      (node (ref "IC10") (pin "13") (pinfunction "I1_13") (pintype "input"))
      (node (ref "IC10") (pin "2") (pinfunction "I1_2") (pintype "input"))
      (node (ref "IC10") (pin "5") (pinfunction "I1_5") (pintype "input"))
      (node (ref "IC5") (pin "7") (pinfunction "C0_7") (pintype "input"))
      (node (ref "IC9") (pin "10") (pinfunction "I1_10") (pintype "input"))
      (node (ref "IC9") (pin "13") (pinfunction "I1_13") (pintype "input"))
      (node (ref "IC9") (pin "2") (pinfunction "I1_2") (pintype "input"))
      (node (ref "IC9") (pin "5") (pinfunction "I1_5") (pintype "input"))
      (node (ref "JP6") (pin "3") (pinfunction "3_3") (pintype "passive"))
    )
    (net (code "161") (name "VCC") (class "Default")
      (node (ref "C1") (pin "1") (pinfunction "1_1") (pintype "passive"))
      (node (ref "C2") (pin "1") (pinfunction "1_1") (pintype "passive"))
      (node (ref "C3") (pin "1") (pinfunction "1_1") (pintype "passive"))
      (node (ref "C4") (pin "1") (pinfunction "1_1") (pintype "passive"))
      (node (ref "C5") (pin "1") (pinfunction "1_1") (pintype "passive"))
      (node (ref "C6") (pin "1") (pinfunction "1_1") (pintype "passive"))
      (node (ref "C7") (pin "1") (pinfunction "1_1") (pintype "passive"))
      (node (ref "IC15") (pin "1") (pinfunction "DIR_1") (pintype "input"))
      (node (ref "IC17") (pin "21") (pinfunction "~{WE}_21") (pintype "input"))
      (node (ref "IC17") (pin "24") (pinfunction "VCC_24") (pintype "power_in"))
      (node (ref "IC18") (pin "12") (pinfunction "K_12") (pintype "input"))
      (node (ref "IC18") (pin "16") (pinfunction "K_16") (pintype "input"))
      (node (ref "IC18") (pin "2") (pinfunction "PRE_2") (pintype "input"))
      (node (ref "IC18") (pin "3") (pinfunction "CLR_3") (pintype "input"))
      (node (ref "IC18") (pin "4") (pinfunction "J_4") (pintype "input"))
      (node (ref "IC18") (pin "7") (pinfunction "PRE_7") (pintype "input"))
      (node (ref "IC18") (pin "8") (pinfunction "CLR_8") (pintype "input"))
      (node (ref "IC18") (pin "9") (pinfunction "J_9") (pintype "input"))
      (node (ref "IC19") (pin "8") (pinfunction "V+_8") (pintype "power_in"))
      (node (ref "IC4") (pin "1") (pinfunction "DIR_1") (pintype "input"))
      (node (ref "IC7") (pin "1") (pinfunction "DIR_1") (pintype "input"))
      (node (ref "JP1") (pin "1") (pinfunction "1_1") (pintype "passive"))
      (node (ref "JP1") (pin "2") (pinfunction "2_2") (pintype "passive"))
      (node (ref "R31") (pin "2") (pinfunction "2_2") (pintype "passive"))
      (node (ref "S1") (pin "3") (pinfunction "S_3") (pintype "passive"))
      (node (ref "S2") (pin "3") (pinfunction "S_3") (pintype "passive"))
    )
    (net (code "162") (name "VDD") (class "Default")
      (node (ref "J1") (pin "1") (pinfunction "1_1") (pintype "passive"))
      (node (ref "Q1") (pin "D") (pinfunction "D_D") (pintype "passive"))
    )
    (net (code "163") (name "ZF") (class "Default")
      (node (ref "IC8") (pin "4") (pinfunction "Q2_4") (pintype "tri_state"))
      (node (ref "JP6") (pin "6") (pinfunction "6_6") (pintype "passive"))
      (node (ref "LED22") (pin "A") (pinfunction "A_A") (pintype "passive"))
    )
    (net (code "164") (name "unconnected-(IC1A-A1-Pad2)") (class "Default")
      (node (ref "IC1") (pin "2") (pinfunction "A1_2") (pintype "bidirectional"))
    )
    (net (code "165") (name "unconnected-(IC1A-A2-Pad3)") (class "Default")
      (node (ref "IC1") (pin "3") (pinfunction "A2_3") (pintype "bidirectional"))
    )
    (net (code "166") (name "unconnected-(IC1A-A3-Pad4)") (class "Default")
      (node (ref "IC1") (pin "4") (pinfunction "A3_4") (pintype "bidirectional"))
    )
    (net (code "167") (name "unconnected-(IC1A-A4-Pad5)") (class "Default")
      (node (ref "IC1") (pin "5") (pinfunction "A4_5") (pintype "bidirectional"))
    )
    (net (code "168") (name "unconnected-(IC1A-B1-Pad18)") (class "Default")
      (node (ref "IC1") (pin "18") (pinfunction "B1_18") (pintype "bidirectional"))
    )
    (net (code "169") (name "unconnected-(IC1A-B2-Pad17)") (class "Default")
      (node (ref "IC1") (pin "17") (pinfunction "B2_17") (pintype "bidirectional"))
    )
    (net (code "170") (name "unconnected-(IC1A-B3-Pad16)") (class "Default")
      (node (ref "IC1") (pin "16") (pinfunction "B3_16") (pintype "bidirectional"))
    )
    (net (code "171") (name "unconnected-(IC1A-B4-Pad15)") (class "Default")
      (node (ref "IC1") (pin "15") (pinfunction "B4_15") (pintype "bidirectional"))
    )
    (net (code "172") (name "unconnected-(IC8A-D3-Pad12)") (class "Default")
      (node (ref "IC8") (pin "12") (pinfunction "D3_12") (pintype "input"))
    )
    (net (code "173") (name "unconnected-(IC8A-D4-Pad11)") (class "Default")
      (node (ref "IC8") (pin "11") (pinfunction "D4_11") (pintype "input"))
    )
    (net (code "174") (name "unconnected-(IC8A-Q3-Pad5)") (class "Default")
      (node (ref "IC8") (pin "5") (pinfunction "Q3_5") (pintype "tri_state"))
    )
    (net (code "175") (name "unconnected-(IC8A-Q4-Pad6)") (class "Default")
      (node (ref "IC8") (pin "6") (pinfunction "Q4_6") (pintype "tri_state"))
    )
    (net (code "176") (name "unconnected-(IC18A-Q-Pad15)") (class "Default")
      (node (ref "IC18") (pin "15") (pinfunction "Q_15") (pintype "output"))
    )
    (net (code "177") (name "unconnected-(IC18B-Q-Pad11)") (class "Default")
      (node (ref "IC18") (pin "11") (pinfunction "Q_11") (pintype "output"))
    )
    (net (code "178") (name "unconnected-(IC19-R-Pad4)") (class "Default")
      (node (ref "IC19") (pin "4") (pinfunction "R_4") (pintype "input"))
    )
    (net (code "179") (name "unconnected-(S2-O-Pad1)") (class "Default")
      (node (ref "S2") (pin "1") (pinfunction "O_1") (pintype "passive"))
    )
    (net (code "180") (name "unconnected-(U2A-RCO-Pad15)") (class "Default")
      (node (ref "U2") (pin "15") (pinfunction "RCO_15") (pintype "output"))
    )
  )
)
